# XMICRO-VDP_V1_1.net
KiCad netlist of a schematic drawn in EAGLE
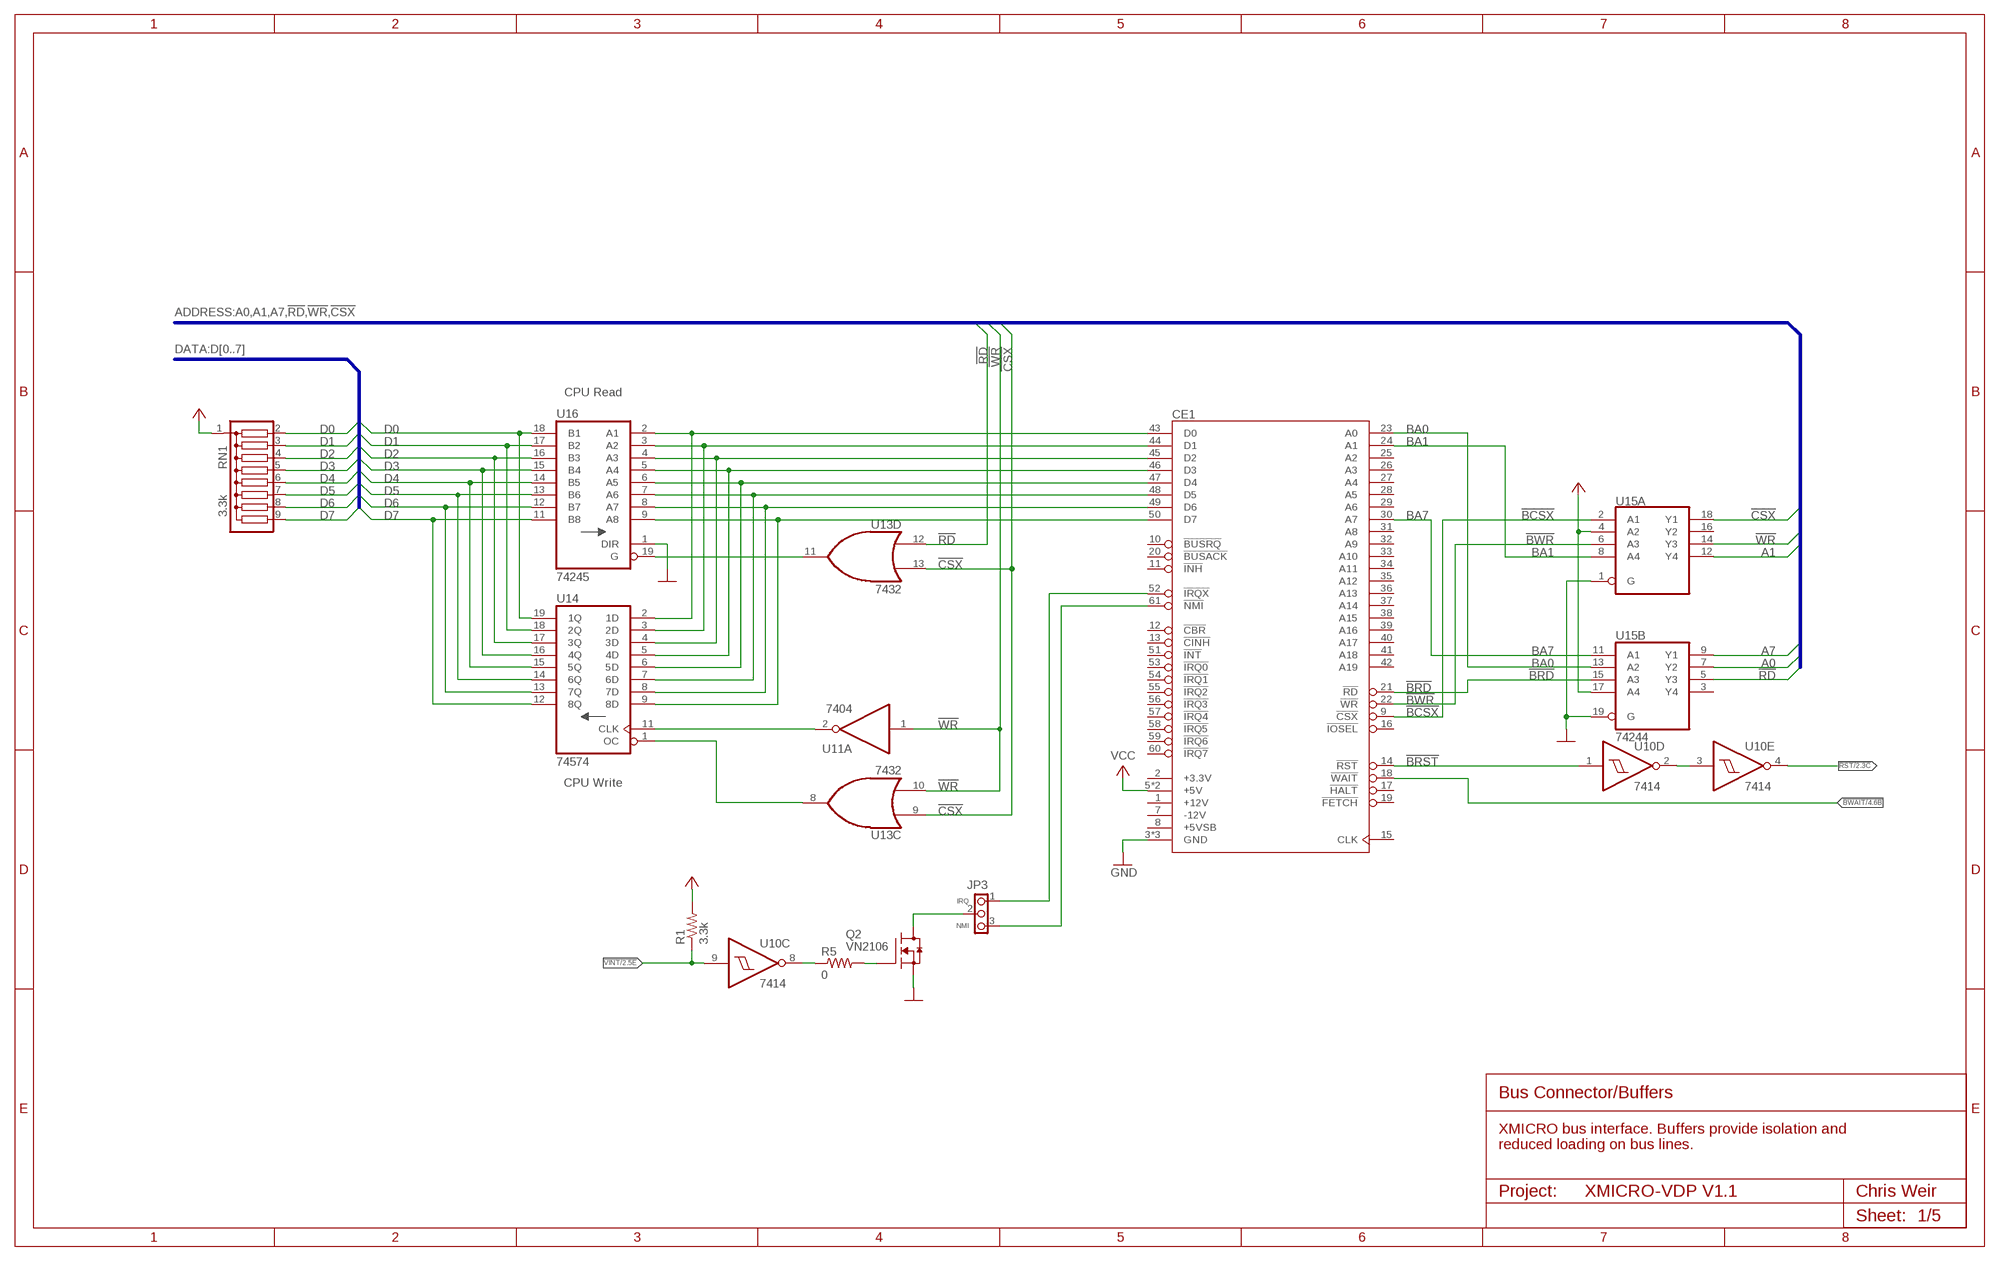
[diagram p0: schematic, sheet 1]
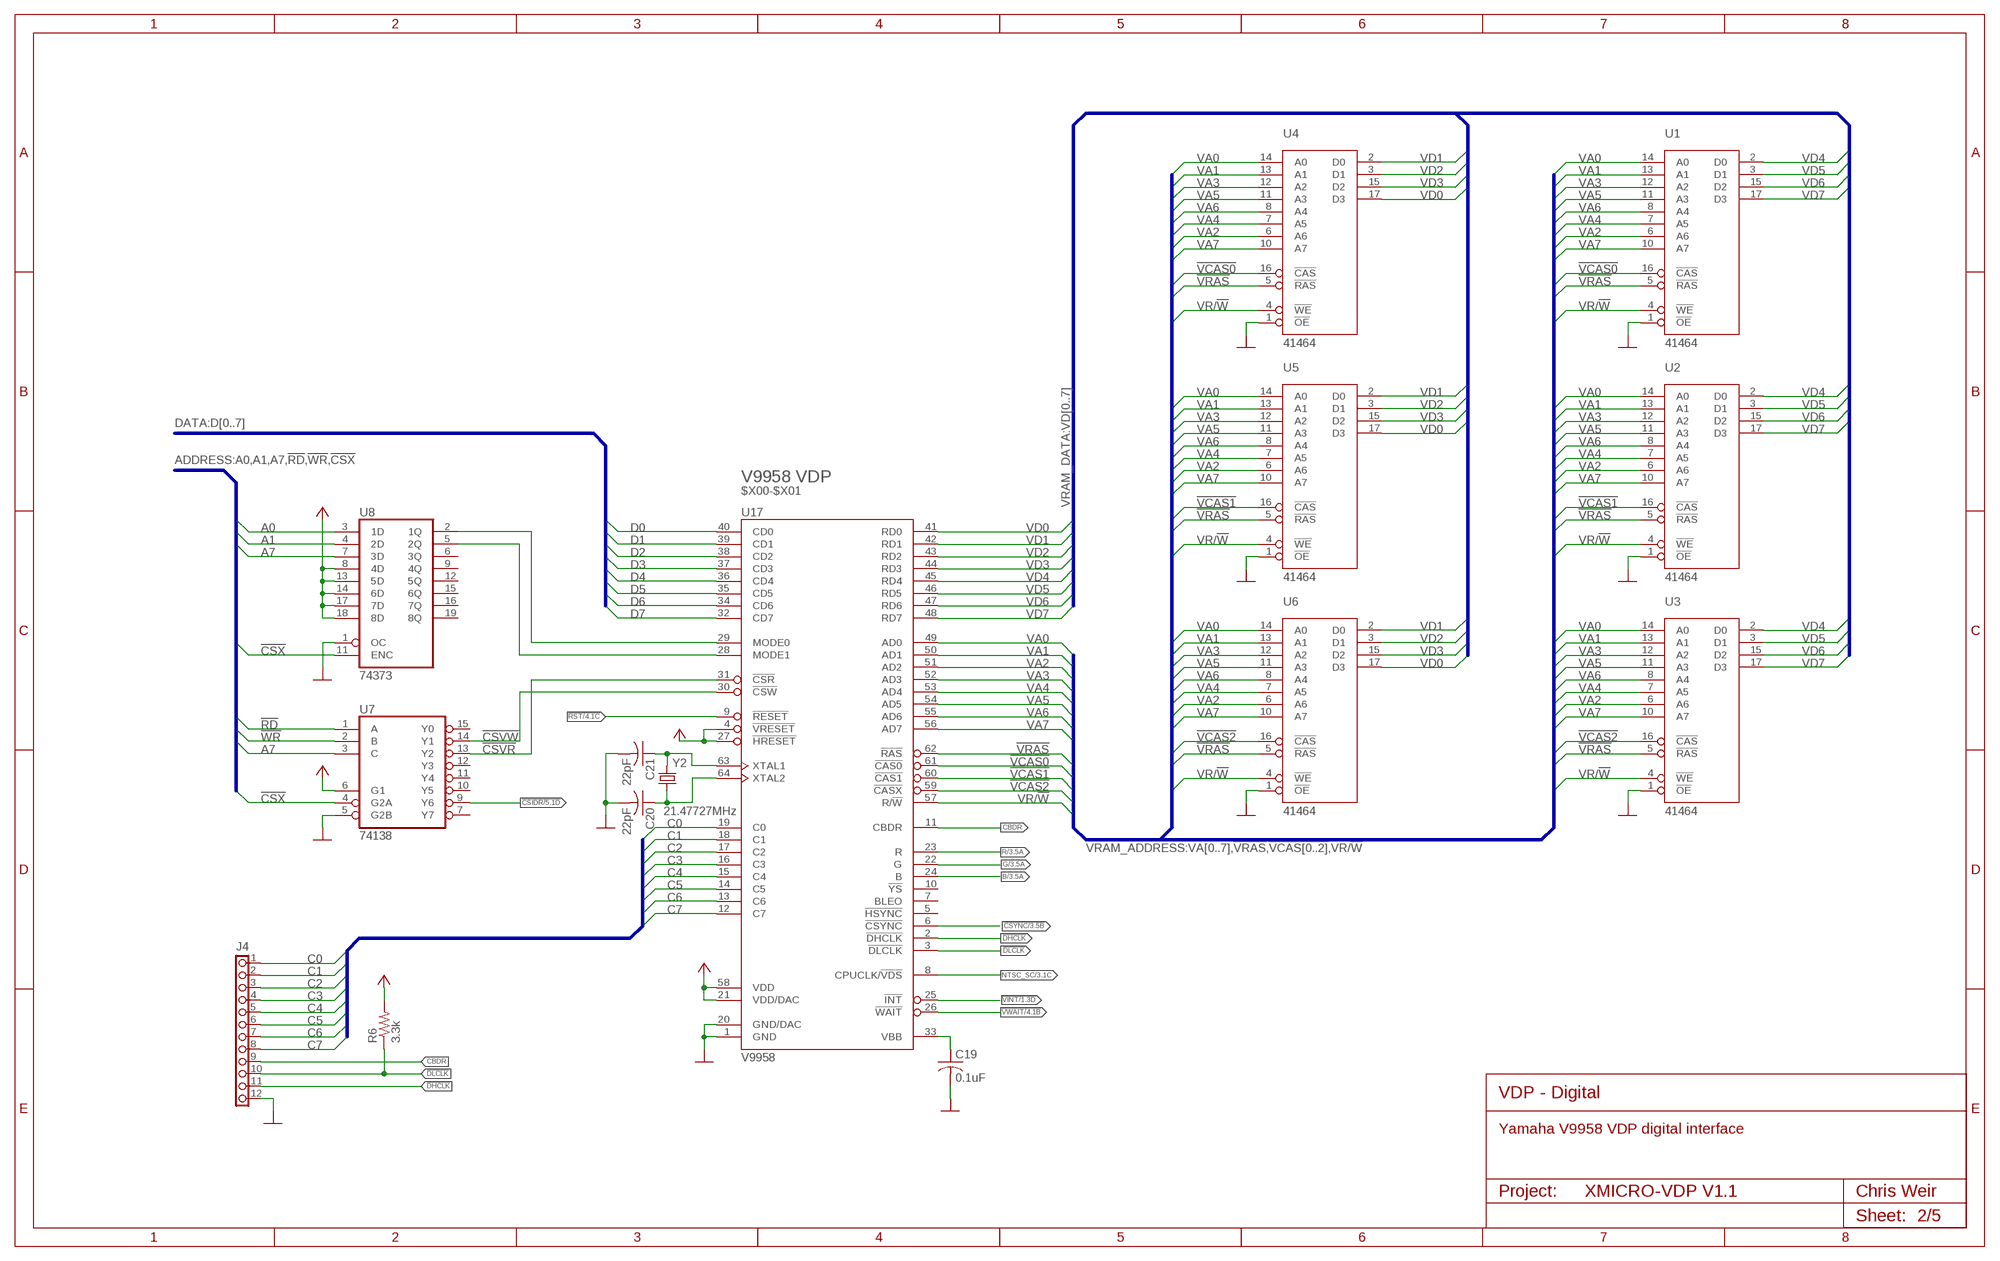
[diagram p1: schematic, sheet 2]
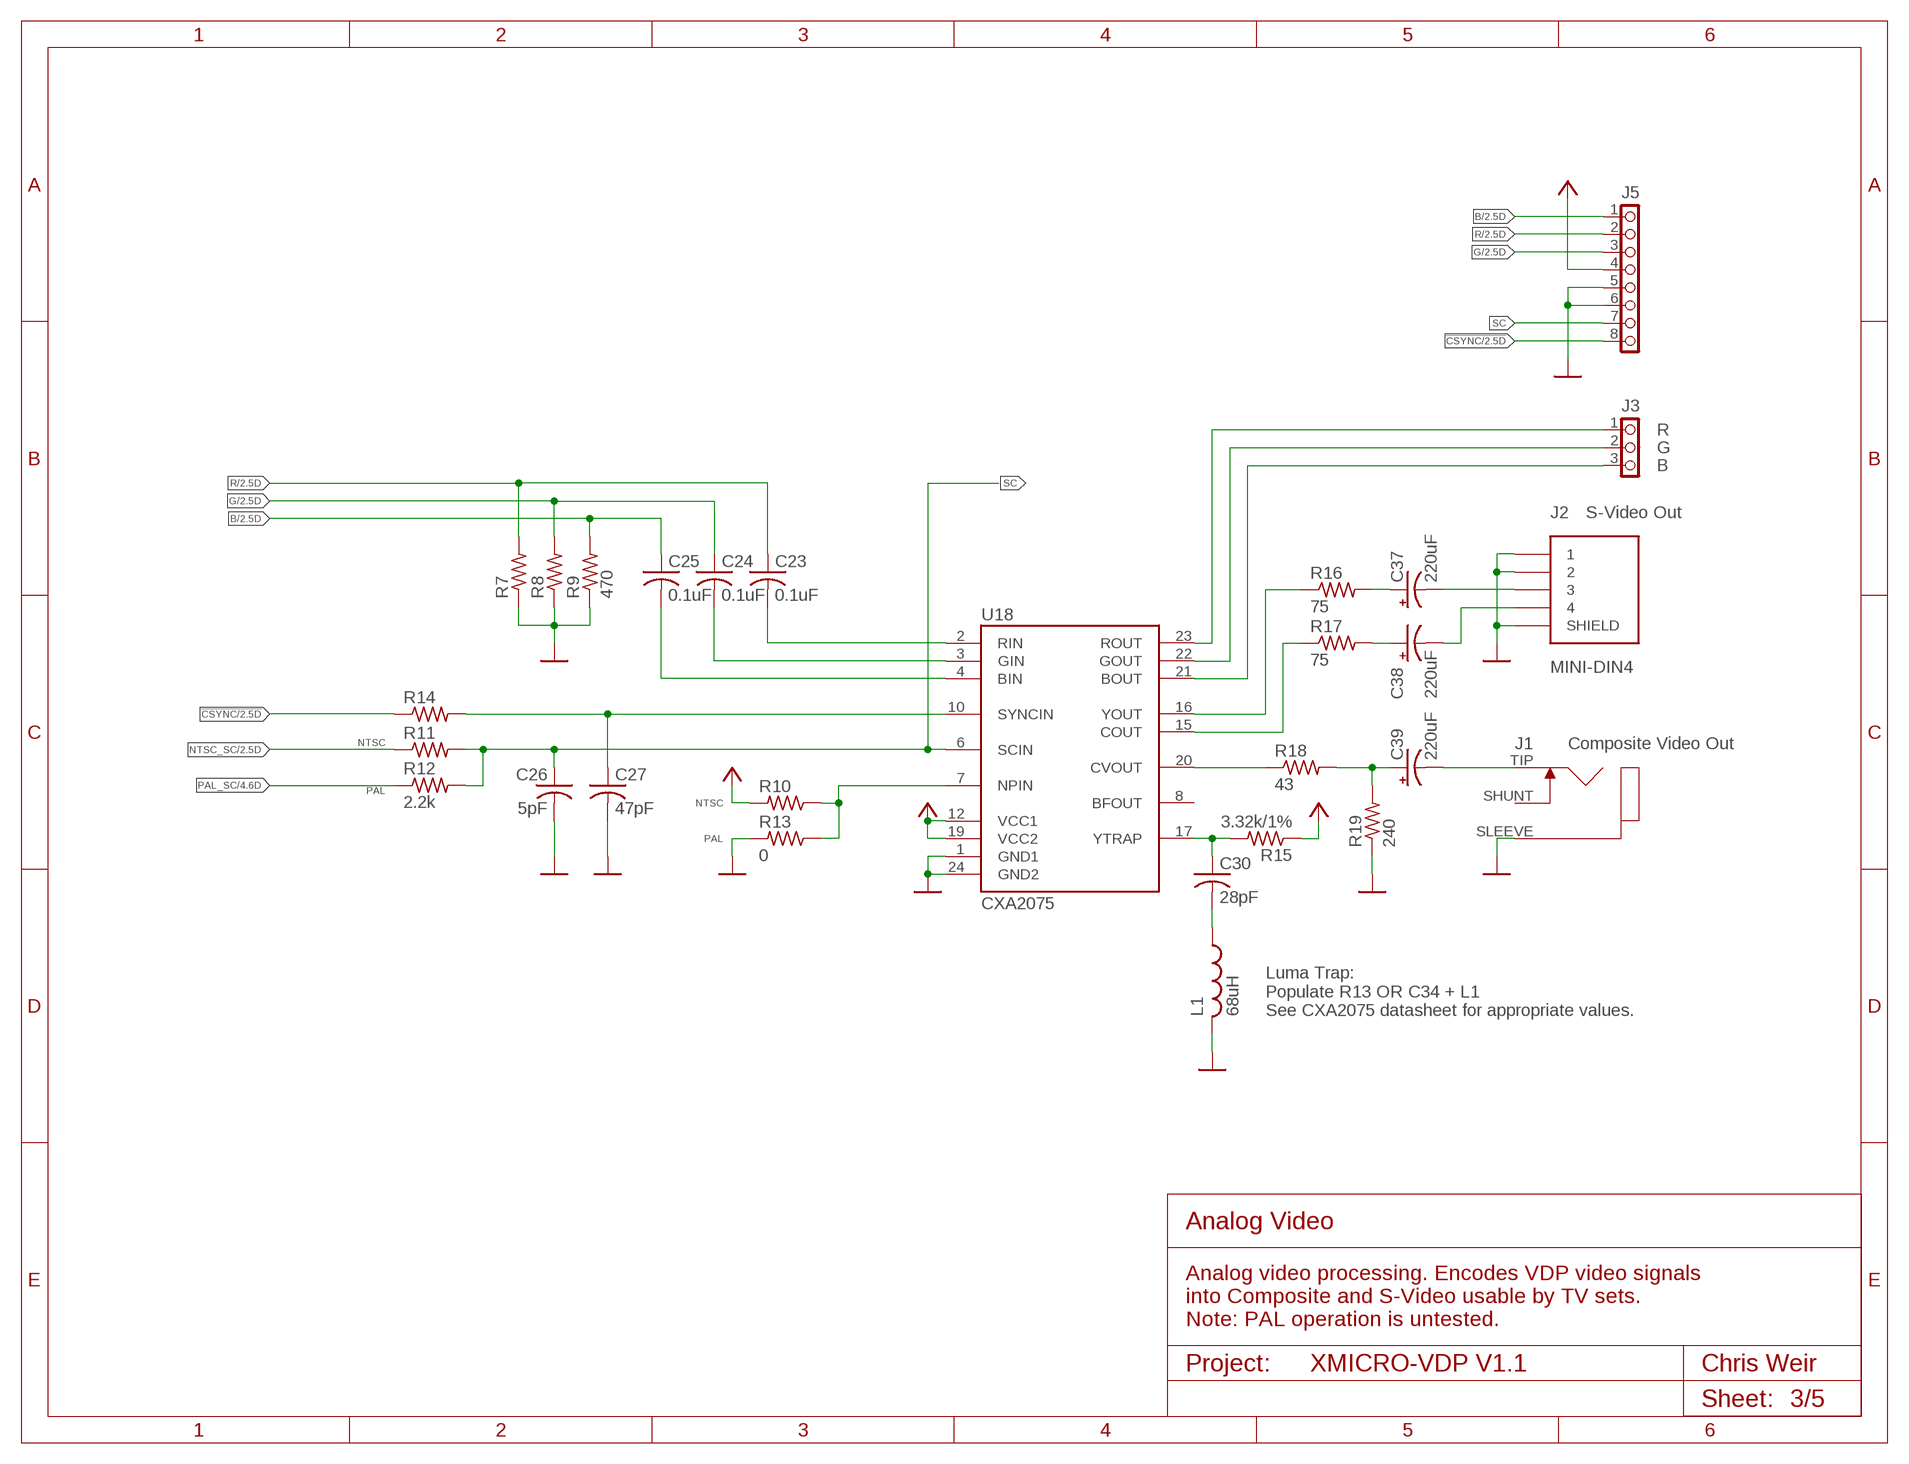
[diagram p2: schematic, sheet 3]
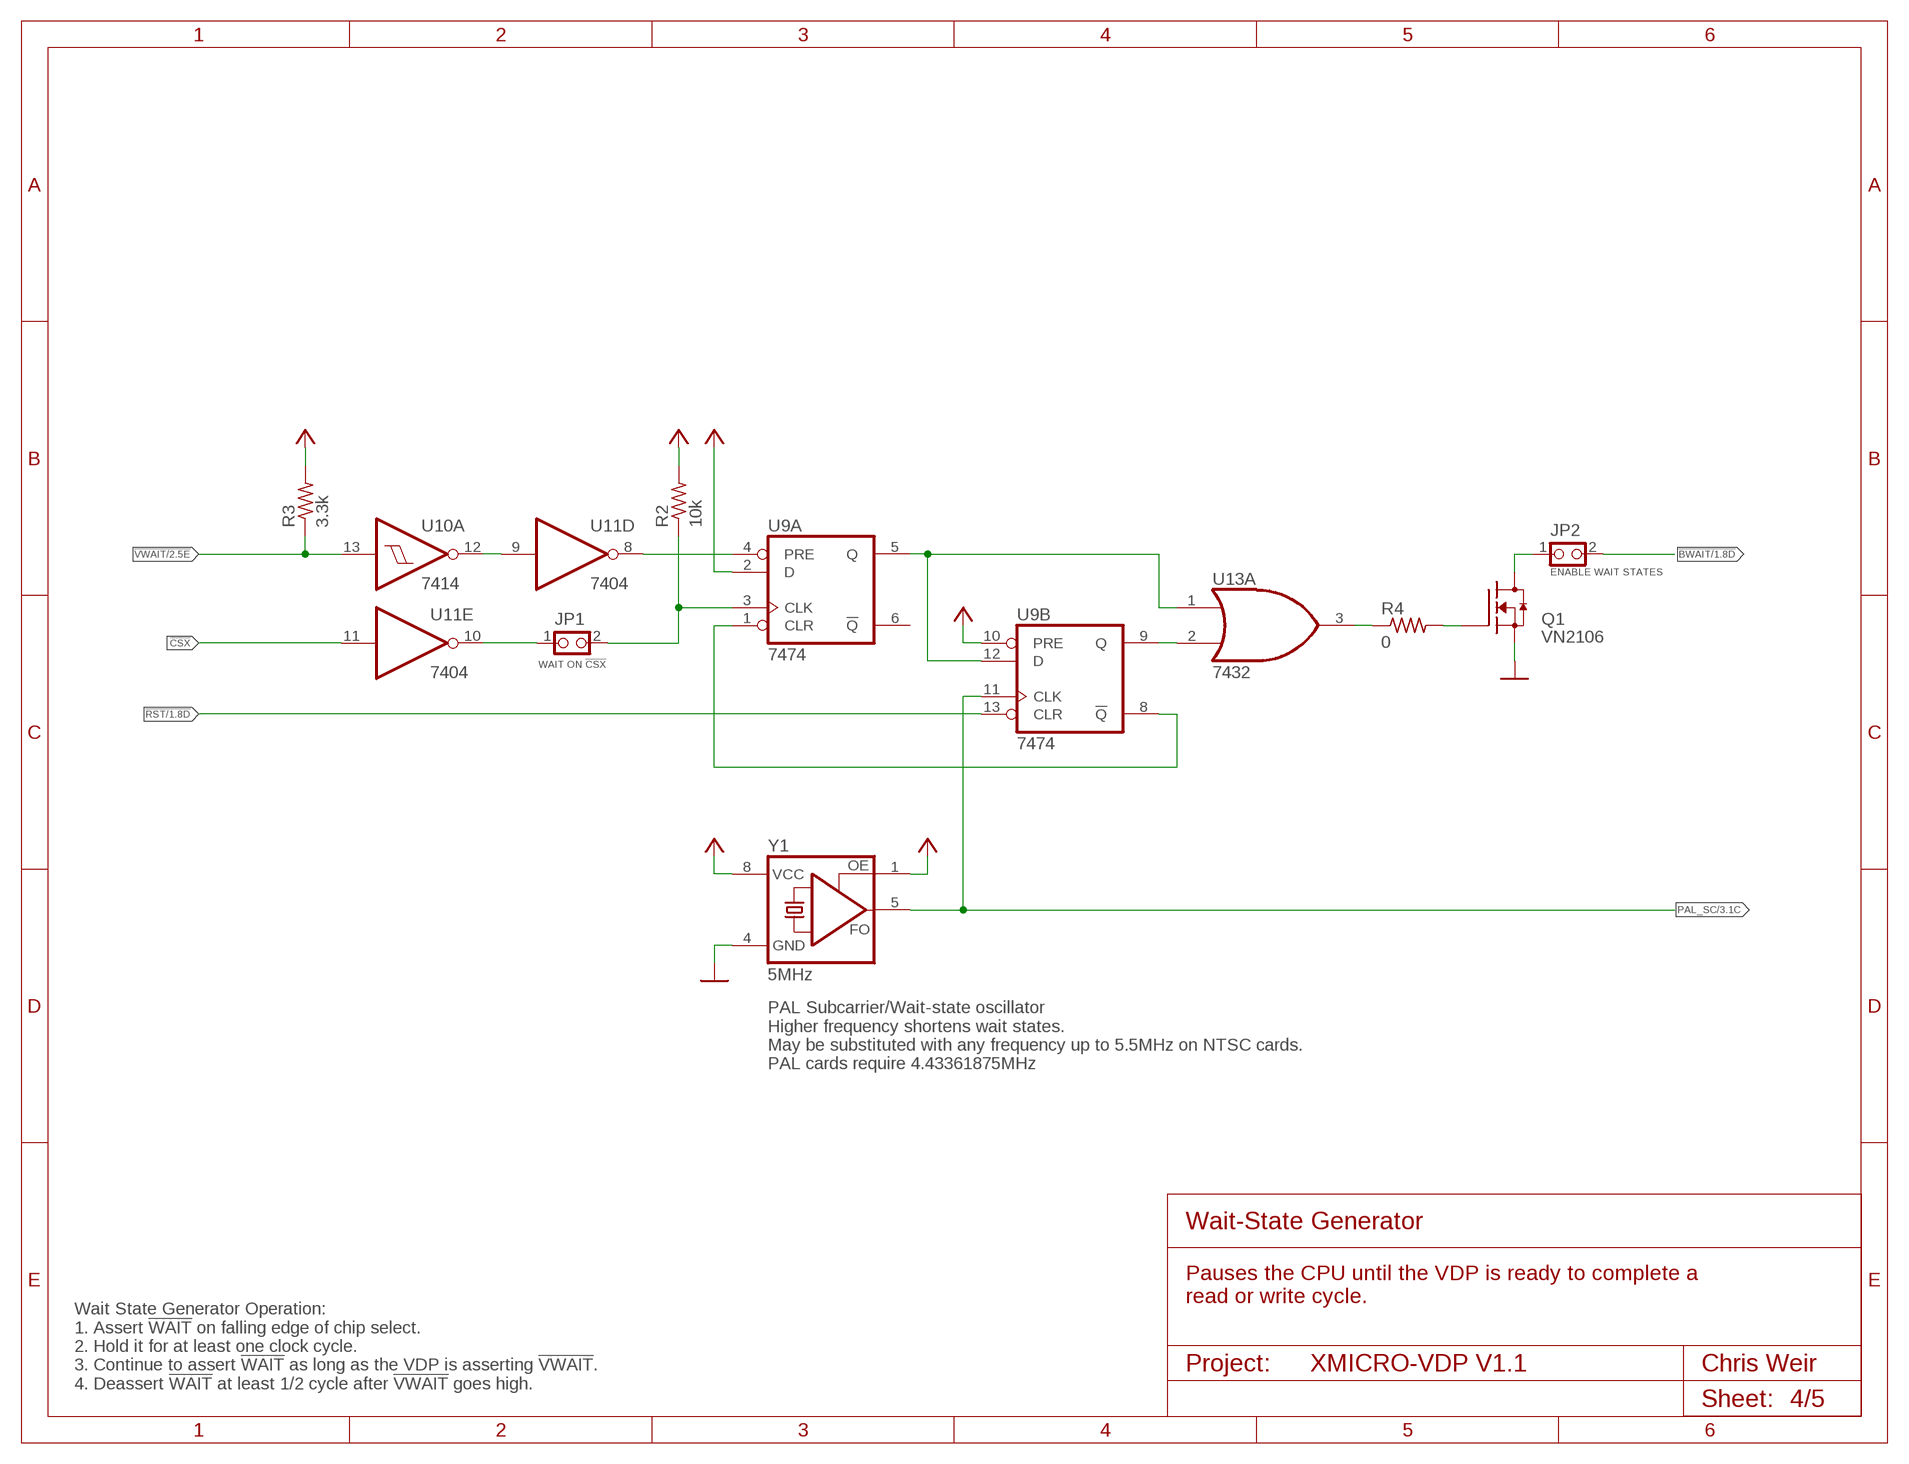
[diagram p3: schematic, sheet 4]
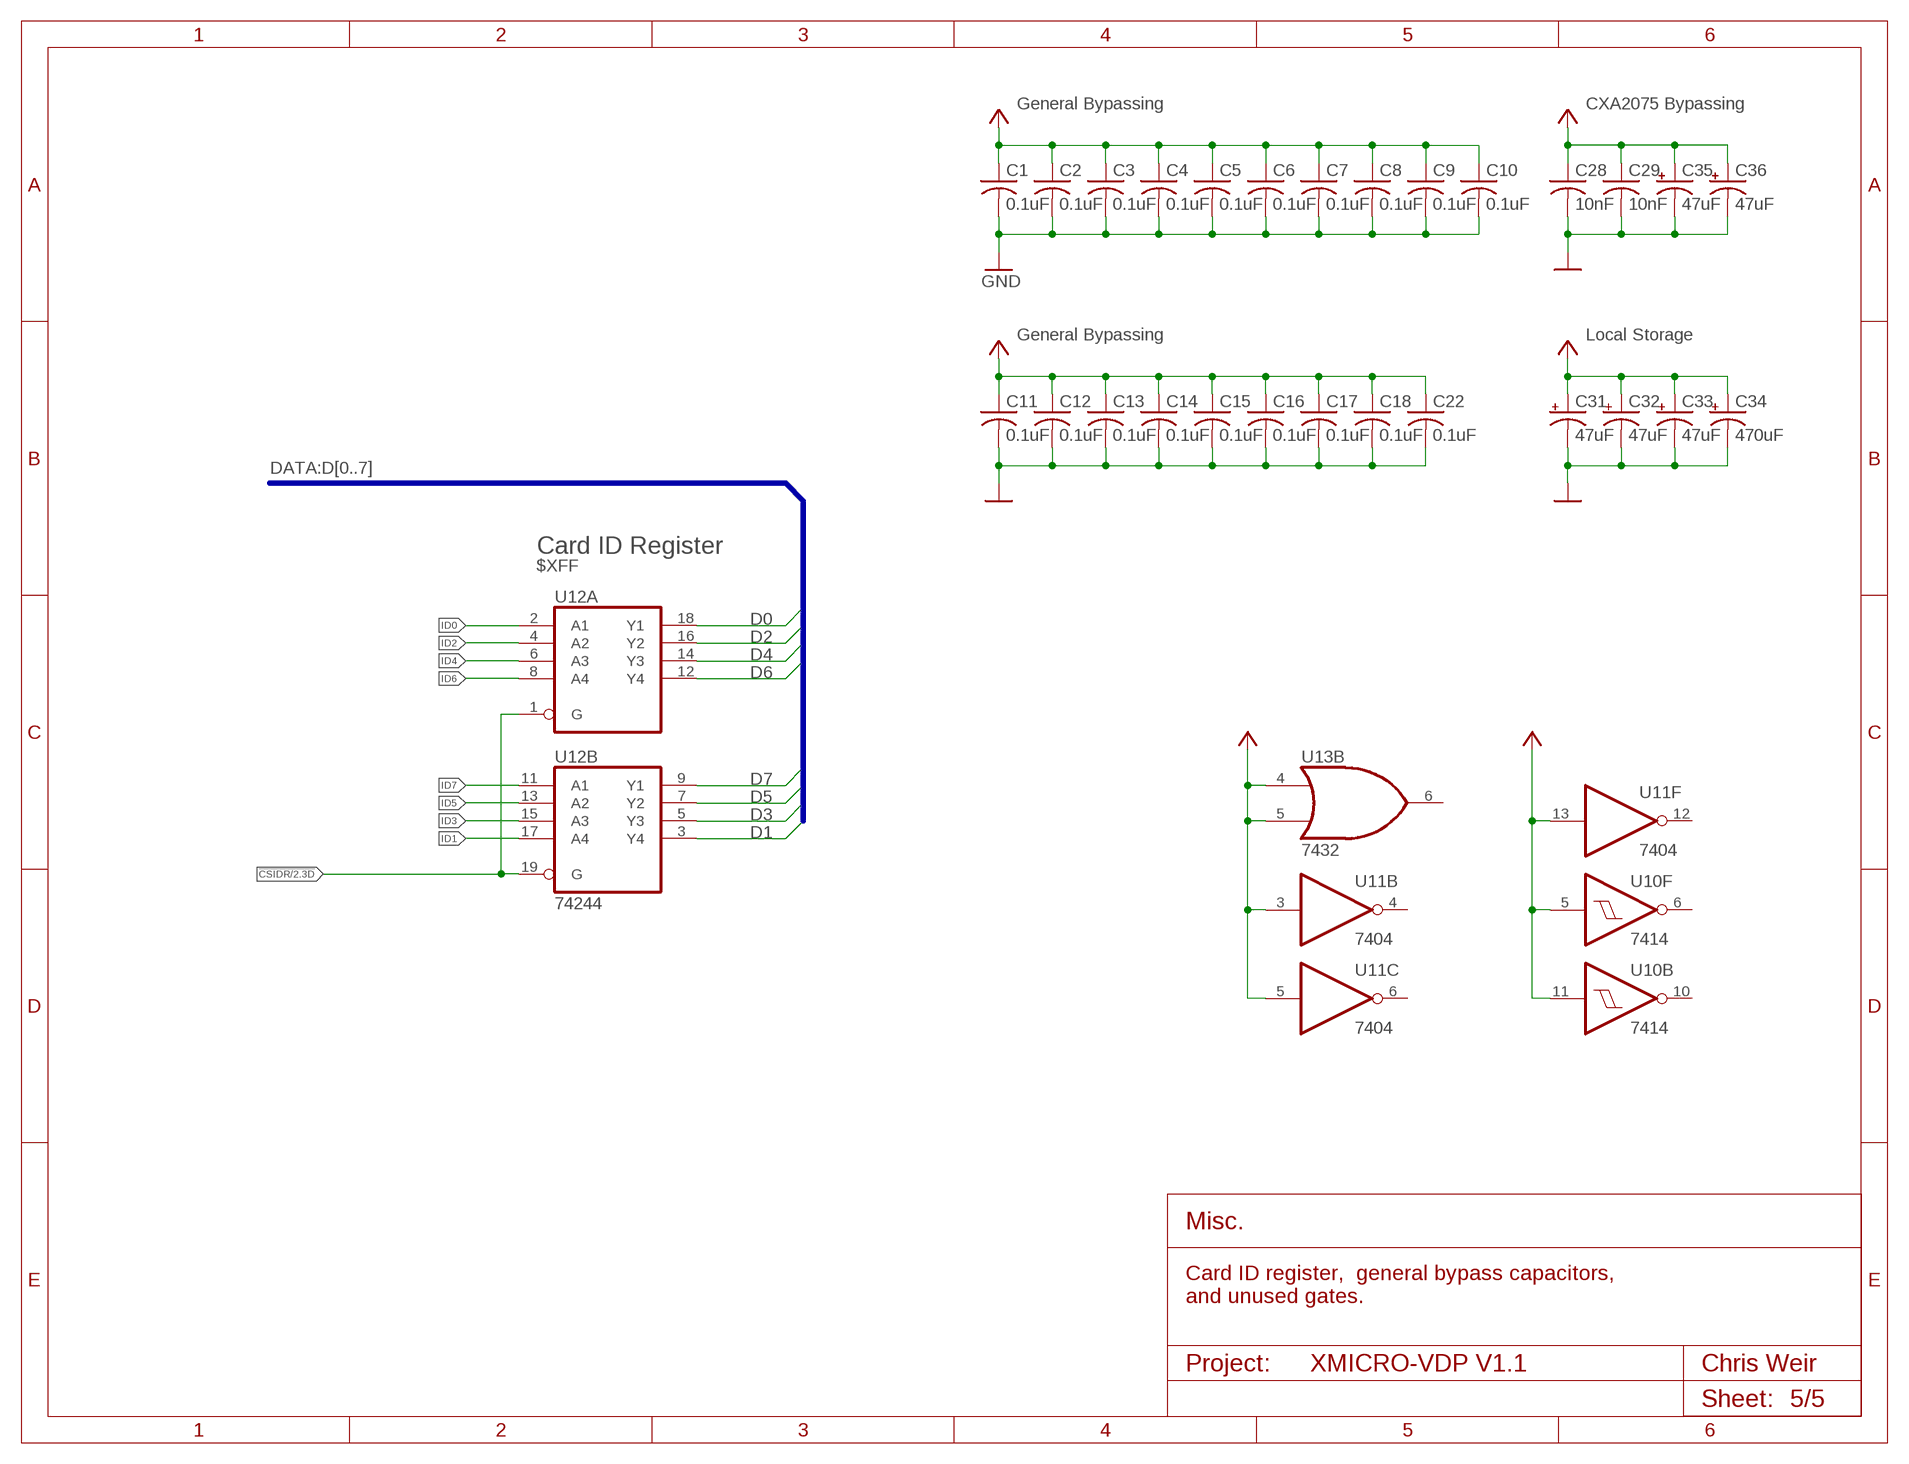
[diagram p4: schematic, sheet 5]

(export (version "E")
  (design (tool "Eeschema 10.0.6"))
  (components
    (comp (ref "C23")
      (value "0.1uF")
      (footprint "eagle-import:C100")
      (libsource (lib "eagle-import") (part "C-US100"))
    )
    (comp (ref "C24")
      (value "0.1uF")
      (footprint "eagle-import:C100")
      (libsource (lib "eagle-import") (part "C-US100"))
    )
    (comp (ref "C25")
      (value "0.1uF")
      (footprint "eagle-import:C100")
      (libsource (lib "eagle-import") (part "C-US100"))
    )
    (comp (ref "C26")
      (value "5pF")
      (footprint "eagle-import:C100")
      (libsource (lib "eagle-import") (part "C-US100"))
    )
    (comp (ref "C27")
      (value "47pF")
      (footprint "eagle-import:C100")
      (libsource (lib "eagle-import") (part "C-US100"))
    )
    (comp (ref "C30")
      (value "28pF")
      (footprint "eagle-import:C100")
      (libsource (lib "eagle-import") (part "C-US100"))
    )
    (comp (ref "C37")
      (value "220uF")
      (footprint "eagle-import:E2,5-7")
      (libsource (lib "eagle-import") (part "CPOL-USE2.5-7"))
    )
    (comp (ref "C38")
      (value "220uF")
      (footprint "eagle-import:E2,5-7")
      (libsource (lib "eagle-import") (part "CPOL-USE2.5-7"))
    )
    (comp (ref "C39")
      (value "220uF")
      (footprint "eagle-import:E2,5-7")
      (libsource (lib "eagle-import") (part "CPOL-USE2.5-7"))
    )
    (comp (ref "J1")
      (value "PJRAN1XU04AUX")
      (footprint "eagle-import:PJRAN1")
      (libsource (lib "eagle-import") (part "PJRAN1"))
    )
    (comp (ref "J2")
      (value "MINI-DIN4")
      (footprint "eagle-import:MINI-DIN4")
      (libsource (lib "eagle-import") (part "MINI-DIN4"))
    )
    (comp (ref "J3")
      (value "PINHD1X3")
      (footprint "eagle-import:1X03")
      (libsource (lib "eagle-import") (part "PINHD1X3"))
    )
    (comp (ref "J5")
      (value "PINHD-1X8")
      (footprint "eagle-import:1X08")
      (libsource (lib "eagle-import") (part "PINHD-1X8"))
    )
    (comp (ref "L1")
      (value "68uH")
      (footprint "eagle-import:0207_10")
      (libsource (lib "eagle-import") (part "L-US0207/10"))
    )
    (comp (ref "R7")
      (value "470")
      (footprint "eagle-import:0207_10")
      (libsource (lib "eagle-import") (part "R-US_0207/10"))
    )
    (comp (ref "R8")
      (value "470")
      (footprint "eagle-import:0207_10")
      (libsource (lib "eagle-import") (part "R-US_0207/10"))
    )
    (comp (ref "R9")
      (value "470")
      (footprint "eagle-import:0207_10")
      (libsource (lib "eagle-import") (part "R-US_0207/10"))
    )
    (comp (ref "R10")
      (value "0")
      (footprint "eagle-import:0207_10")
      (libsource (lib "eagle-import") (part "R-US_0207/10"))
    )
    (comp (ref "R11")
      (value "2.2k")
      (footprint "eagle-import:0207_10")
      (libsource (lib "eagle-import") (part "R-US_0207/10"))
    )
    (comp (ref "R12")
      (value "2.2k")
      (footprint "eagle-import:0207_10")
      (libsource (lib "eagle-import") (part "R-US_0207/10"))
    )
    (comp (ref "R13")
      (value "0")
      (footprint "eagle-import:0207_10")
      (libsource (lib "eagle-import") (part "R-US_0207/10"))
    )
    (comp (ref "R14")
      (value "2.2k")
      (footprint "eagle-import:0207_10")
      (libsource (lib "eagle-import") (part "R-US_0207/10"))
    )
    (comp (ref "R15")
      (value "3.32k/1%")
      (footprint "eagle-import:0207_10")
      (libsource (lib "eagle-import") (part "R-US_0207/10"))
    )
    (comp (ref "R16")
      (value "75")
      (footprint "eagle-import:0207_10")
      (libsource (lib "eagle-import") (part "R-US_0207/10"))
    )
    (comp (ref "R17")
      (value "75")
      (footprint "eagle-import:0207_10")
      (libsource (lib "eagle-import") (part "R-US_0207/10"))
    )
    (comp (ref "R18")
      (value "43")
      (footprint "eagle-import:0207_10")
      (libsource (lib "eagle-import") (part "R-US_0207/10"))
    )
    (comp (ref "R19")
      (value "240")
      (footprint "eagle-import:0207_10")
      (libsource (lib "eagle-import") (part "R-US_0207/10"))
    )
    (comp (ref "U18")
      (value "CXA2075")
      (footprint "eagle-import:SOP-24")
      (libsource (lib "eagle-import") (part "CXA2075"))
    )
    (comp (ref "JP1")
      (value "PINHD-1X2THRU")
      (footprint "eagle-import:1X02")
      (libsource (lib "eagle-import") (part "PINHD-1X2THRU"))
    )
    (comp (ref "JP2")
      (value "PINHD-1X2THRU")
      (footprint "eagle-import:1X02")
      (libsource (lib "eagle-import") (part "PINHD-1X2THRU"))
    )
    (comp (ref "Q1")
      (value "VN2106")
      (footprint "eagle-import:TO92")
      (libsource (lib "eagle-import") (part "VN2106"))
    )
    (comp (ref "R2")
      (value "10k")
      (footprint "eagle-import:0207_10")
      (libsource (lib "eagle-import") (part "R-US_0207/10"))
    )
    (comp (ref "R3")
      (value "3.3k")
      (footprint "eagle-import:0207_10")
      (libsource (lib "eagle-import") (part "R-US_0207/10"))
    )
    (comp (ref "R4")
      (value "0")
      (footprint "eagle-import:0207_10")
      (libsource (lib "eagle-import") (part "R-US_0207/10"))
    )
    (comp (ref "U9")
      (value "7474")
      (footprint "eagle-import:DIL14")
      (libsource (lib "eagle-import") (part "7474NLS"))
    )
    (comp (ref "U10")
      (value "7414")
      (footprint "eagle-import:DIL14")
      (libsource (lib "eagle-import") (part "7414NLS"))
    )
    (comp (ref "U11")
      (value "7404")
      (footprint "eagle-import:DIL14")
      (libsource (lib "eagle-import") (part "7404NLS"))
    )
    (comp (ref "U13")
      (value "7432")
      (footprint "eagle-import:DIL14")
      (libsource (lib "eagle-import") (part "7432NLS"))
    )
    (comp (ref "Y1")
      (value "5MHz")
      (footprint "eagle-import:DIL08S")
      (libsource (lib "eagle-import") (part "OSC-OE"))
    )
    (comp (ref "CE1")
      (value "XMICRO-BUS-EDGE62M")
      (footprint "eagle-import:EDGE62M")
      (libsource (lib "eagle-import") (part "XMICRO-BUS-EDGE62M"))
    )
    (comp (ref "JP3")
      (value "PINHD1X3THRU")
      (footprint "eagle-import:1X03")
      (libsource (lib "eagle-import") (part "PINHD1X3THRU"))
    )
    (comp (ref "Q2")
      (value "VN2106")
      (footprint "eagle-import:TO92")
      (libsource (lib "eagle-import") (part "VN2106"))
    )
    (comp (ref "R1")
      (value "3.3k")
      (footprint "eagle-import:0207_10")
      (libsource (lib "eagle-import") (part "R-US_0207/10"))
    )
    (comp (ref "R5")
      (value "0")
      (footprint "eagle-import:0207_10")
      (libsource (lib "eagle-import") (part "R-US_0207/10"))
    )
    (comp (ref "RN1")
      (value "3.3k")
      (footprint "eagle-import:SIL9")
      (libsource (lib "eagle-import") (part "RN8"))
    )
    (comp (ref "U14")
      (value "74574")
      (footprint "eagle-import:DIL20")
      (libsource (lib "eagle-import") (part "74574NHC"))
    )
    (comp (ref "U15")
      (value "74244")
      (footprint "eagle-import:DIL20")
      (libsource (lib "eagle-import") (part "74244NLS"))
    )
    (comp (ref "U16")
      (value "74245")
      (footprint "eagle-import:DIL20")
      (libsource (lib "eagle-import") (part "74245NLS"))
    )
    (comp (ref "C19")
      (value "0.1uF")
      (footprint "eagle-import:C100")
      (libsource (lib "eagle-import") (part "C-US100"))
    )
    (comp (ref "C20")
      (value "22pF")
      (footprint "eagle-import:C100")
      (libsource (lib "eagle-import") (part "C-US100"))
    )
    (comp (ref "C21")
      (value "22pF")
      (footprint "eagle-import:C100")
      (libsource (lib "eagle-import") (part "C-US100"))
    )
    (comp (ref "J4")
      (value "PINHD-2X6")
      (footprint "eagle-import:2X06")
      (libsource (lib "eagle-import") (part "PINHD-2X6"))
    )
    (comp (ref "R6")
      (value "3.3k")
      (footprint "eagle-import:0207_10")
      (libsource (lib "eagle-import") (part "R-US_0207/10"))
    )
    (comp (ref "U1")
      (value "41464")
      (footprint "eagle-import:DIL18")
      (libsource (lib "eagle-import") (part "41464"))
    )
    (comp (ref "U2")
      (value "41464")
      (footprint "eagle-import:DIL18")
      (libsource (lib "eagle-import") (part "41464"))
    )
    (comp (ref "U3")
      (value "41464")
      (footprint "eagle-import:DIL18")
      (libsource (lib "eagle-import") (part "41464"))
    )
    (comp (ref "U4")
      (value "41464")
      (footprint "eagle-import:DIL18")
      (libsource (lib "eagle-import") (part "41464"))
    )
    (comp (ref "U5")
      (value "41464")
      (footprint "eagle-import:DIL18")
      (libsource (lib "eagle-import") (part "41464"))
    )
    (comp (ref "U6")
      (value "41464")
      (footprint "eagle-import:DIL18")
      (libsource (lib "eagle-import") (part "41464"))
    )
    (comp (ref "U7")
      (value "74138")
      (footprint "eagle-import:DIL16")
      (libsource (lib "eagle-import") (part "74138NS"))
    )
    (comp (ref "U8")
      (value "74373")
      (footprint "eagle-import:DIL20")
      (libsource (lib "eagle-import") (part "74373NLS"))
    )
    (comp (ref "U17")
      (value "V9958")
      (footprint "eagle-import:SDIP64")
      (libsource (lib "eagle-import") (part "V9958"))
    )
    (comp (ref "Y2")
      (value "21.47727MHz")
      (footprint "eagle-import:HC-49US")
      (libsource (lib "eagle-import") (part "CRYSTAL"))
    )
    (comp (ref "C1")
      (value "0.1uF")
      (footprint "eagle-import:C100")
      (libsource (lib "eagle-import") (part "C-US100"))
    )
    (comp (ref "C2")
      (value "0.1uF")
      (footprint "eagle-import:C100")
      (libsource (lib "eagle-import") (part "C-US100"))
    )
    (comp (ref "C3")
      (value "0.1uF")
      (footprint "eagle-import:C100")
      (libsource (lib "eagle-import") (part "C-US100"))
    )
    (comp (ref "C4")
      (value "0.1uF")
      (footprint "eagle-import:C100")
      (libsource (lib "eagle-import") (part "C-US100"))
    )
    (comp (ref "C5")
      (value "0.1uF")
      (footprint "eagle-import:C100")
      (libsource (lib "eagle-import") (part "C-US100"))
    )
    (comp (ref "C6")
      (value "0.1uF")
      (footprint "eagle-import:C100")
      (libsource (lib "eagle-import") (part "C-US100"))
    )
    (comp (ref "C7")
      (value "0.1uF")
      (footprint "eagle-import:C100")
      (libsource (lib "eagle-import") (part "C-US100"))
    )
    (comp (ref "C8")
      (value "0.1uF")
      (footprint "eagle-import:C100")
      (libsource (lib "eagle-import") (part "C-US100"))
    )
    (comp (ref "C9")
      (value "0.1uF")
      (footprint "eagle-import:C100")
      (libsource (lib "eagle-import") (part "C-US100"))
    )
    (comp (ref "C10")
      (value "0.1uF")
      (footprint "eagle-import:C100")
      (libsource (lib "eagle-import") (part "C-US100"))
    )
    (comp (ref "C11")
      (value "0.1uF")
      (footprint "eagle-import:C100")
      (libsource (lib "eagle-import") (part "C-US100"))
    )
    (comp (ref "C12")
      (value "0.1uF")
      (footprint "eagle-import:C100")
      (libsource (lib "eagle-import") (part "C-US100"))
    )
    (comp (ref "C13")
      (value "0.1uF")
      (footprint "eagle-import:C100")
      (libsource (lib "eagle-import") (part "C-US100"))
    )
    (comp (ref "C14")
      (value "0.1uF")
      (footprint "eagle-import:C100")
      (libsource (lib "eagle-import") (part "C-US100"))
    )
    (comp (ref "C15")
      (value "0.1uF")
      (footprint "eagle-import:C100")
      (libsource (lib "eagle-import") (part "C-US100"))
    )
    (comp (ref "C16")
      (value "0.1uF")
      (footprint "eagle-import:C100")
      (libsource (lib "eagle-import") (part "C-US100"))
    )
    (comp (ref "C17")
      (value "0.1uF")
      (footprint "eagle-import:C100")
      (libsource (lib "eagle-import") (part "C-US100"))
    )
    (comp (ref "C18")
      (value "0.1uF")
      (footprint "eagle-import:C100")
      (libsource (lib "eagle-import") (part "C-US100"))
    )
    (comp (ref "C22")
      (value "0.1uF")
      (footprint "eagle-import:C100")
      (libsource (lib "eagle-import") (part "C-US100"))
    )
    (comp (ref "C28")
      (value "10nF")
      (footprint "eagle-import:C100")
      (libsource (lib "eagle-import") (part "C-US100"))
    )
    (comp (ref "C29")
      (value "10nF")
      (footprint "eagle-import:C050-024X044")
      (libsource (lib "eagle-import") (part "C-US050-024X044"))
    )
    (comp (ref "C31")
      (value "47uF")
      (footprint "eagle-import:E2,5-6")
      (libsource (lib "eagle-import") (part "CPOL-USE2.5-6"))
    )
    (comp (ref "C32")
      (value "47uF")
      (footprint "eagle-import:E2,5-6")
      (libsource (lib "eagle-import") (part "CPOL-USE2.5-6"))
    )
    (comp (ref "C33")
      (value "47uF")
      (footprint "eagle-import:E2,5-6")
      (libsource (lib "eagle-import") (part "CPOL-USE2.5-6"))
    )
    (comp (ref "C34")
      (value "470uF")
      (footprint "eagle-import:C-10-5")
      (libsource (lib "eagle-import") (part "CPOL-US-10-5"))
    )
    (comp (ref "C35")
      (value "47uF")
      (footprint "eagle-import:E2,5-6")
      (libsource (lib "eagle-import") (part "CPOL-USE2.5-6"))
    )
    (comp (ref "C36")
      (value "47uF")
      (footprint "eagle-import:E2,5-6")
      (libsource (lib "eagle-import") (part "CPOL-USE2.5-6"))
    )
    (comp (ref "U12")
      (value "74244")
      (footprint "eagle-import:DIL20")
      (libsource (lib "eagle-import") (part "74244NLS"))
    )
  )
  (nets
    (net (code "42") (name "A0") (class "Default")
      (node (ref "U15") (pin "7") (pinfunction "Y2_7") (pintype "tri_state"))
      (node (ref "U8") (pin "3") (pinfunction "1D_3") (pintype "input"))
    )
    (net (code "43") (name "A1") (class "Default")
      (node (ref "U15") (pin "12") (pinfunction "Y4_12") (pintype "tri_state"))
      (node (ref "U8") (pin "4") (pinfunction "2D_4") (pintype "input"))
    )
    (net (code "44") (name "A7") (class "Default")
      (node (ref "U15") (pin "9") (pinfunction "Y1_9") (pintype "tri_state"))
      (node (ref "U7") (pin "3") (pinfunction "C_3") (pintype "input"))
      (node (ref "U8") (pin "7") (pinfunction "3D_7") (pintype "input"))
    )
    (net (code "45") (name "B") (class "Default")
      (node (ref "C25") (pin "P$1") (pinfunction "1_P$1") (pintype "passive"))
      (node (ref "J5") (pin "1") (pinfunction "1_1") (pintype "passive"))
      (node (ref "R9") (pin "2") (pinfunction "2_2") (pintype "passive"))
      (node (ref "U17") (pin "24") (pinfunction "B_24") (pintype "output"))
    )
    (net (code "46") (name "BA0") (class "Default")
      (node (ref "CE1") (pin "23") (pinfunction "A0_23") (pintype "bidirectional"))
      (node (ref "U15") (pin "13") (pinfunction "A2_13") (pintype "input"))
    )
    (net (code "47") (name "BA1") (class "Default")
      (node (ref "CE1") (pin "24") (pinfunction "A1_24") (pintype "bidirectional"))
      (node (ref "U15") (pin "8") (pinfunction "A4_8") (pintype "input"))
    )
    (net (code "48") (name "BA7") (class "Default")
      (node (ref "CE1") (pin "30") (pinfunction "A7_30") (pintype "bidirectional"))
      (node (ref "U15") (pin "11") (pinfunction "A1_11") (pintype "input"))
    )
    (net (code "49") (name "C0") (class "Default")
      (node (ref "J4") (pin "1") (pinfunction "1_1") (pintype "passive"))
      (node (ref "U17") (pin "19") (pinfunction "C0_19") (pintype "bidirectional"))
    )
    (net (code "50") (name "C1") (class "Default")
      (node (ref "J4") (pin "2") (pinfunction "2_2") (pintype "passive"))
      (node (ref "U17") (pin "18") (pinfunction "C1_18") (pintype "bidirectional"))
    )
    (net (code "51") (name "C2") (class "Default")
      (node (ref "J4") (pin "3") (pinfunction "3_3") (pintype "passive"))
      (node (ref "U17") (pin "17") (pinfunction "C2_17") (pintype "bidirectional"))
    )
    (net (code "52") (name "C3") (class "Default")
      (node (ref "J4") (pin "4") (pinfunction "4_4") (pintype "passive"))
      (node (ref "U17") (pin "16") (pinfunction "C3_16") (pintype "bidirectional"))
    )
    (net (code "53") (name "C4") (class "Default")
      (node (ref "J4") (pin "5") (pinfunction "5_5") (pintype "passive"))
      (node (ref "U17") (pin "15") (pinfunction "C4_15") (pintype "bidirectional"))
    )
    (net (code "54") (name "C5") (class "Default")
      (node (ref "J4") (pin "6") (pinfunction "6_6") (pintype "passive"))
      (node (ref "U17") (pin "14") (pinfunction "C5_14") (pintype "bidirectional"))
    )
    (net (code "55") (name "C6") (class "Default")
      (node (ref "J4") (pin "7") (pinfunction "7_7") (pintype "passive"))
      (node (ref "U17") (pin "13") (pinfunction "C6_13") (pintype "bidirectional"))
    )
    (net (code "56") (name "C7") (class "Default")
      (node (ref "J4") (pin "8") (pinfunction "8_8") (pintype "passive"))
      (node (ref "U17") (pin "12") (pinfunction "C7_12") (pintype "bidirectional"))
    )
    (net (code "57") (name "CBDR") (class "Default")
      (node (ref "J4") (pin "9") (pinfunction "9_9") (pintype "passive"))
      (node (ref "U17") (pin "11") (pinfunction "CBDR_11") (pintype "output"))
    )
    (net (code "58") (name "D0") (class "Default")
      (node (ref "RN1") (pin "2") (pinfunction "2_2") (pintype "passive"))
      (node (ref "U12") (pin "18") (pinfunction "Y1_18") (pintype "tri_state"))
      (node (ref "U14") (pin "19") (pinfunction "1Q_19") (pintype "tri_state"))
      (node (ref "U16") (pin "18") (pinfunction "B1_18") (pintype "bidirectional"))
      (node (ref "U17") (pin "40") (pinfunction "CD0_40") (pintype "bidirectional"))
    )
    (net (code "59") (name "D1") (class "Default")
      (node (ref "RN1") (pin "3") (pinfunction "3_3") (pintype "passive"))
      (node (ref "U12") (pin "3") (pinfunction "Y4_3") (pintype "tri_state"))
      (node (ref "U14") (pin "18") (pinfunction "2Q_18") (pintype "tri_state"))
      (node (ref "U16") (pin "17") (pinfunction "B2_17") (pintype "bidirectional"))
      (node (ref "U17") (pin "39") (pinfunction "CD1_39") (pintype "bidirectional"))
    )
    (net (code "60") (name "D2") (class "Default")
      (node (ref "RN1") (pin "4") (pinfunction "4_4") (pintype "passive"))
      (node (ref "U12") (pin "16") (pinfunction "Y2_16") (pintype "tri_state"))
      (node (ref "U14") (pin "17") (pinfunction "3Q_17") (pintype "tri_state"))
      (node (ref "U16") (pin "16") (pinfunction "B3_16") (pintype "bidirectional"))
      (node (ref "U17") (pin "38") (pinfunction "CD2_38") (pintype "bidirectional"))
    )
    (net (code "61") (name "D3") (class "Default")
      (node (ref "RN1") (pin "5") (pinfunction "5_5") (pintype "passive"))
      (node (ref "U12") (pin "5") (pinfunction "Y3_5") (pintype "tri_state"))
      (node (ref "U14") (pin "16") (pinfunction "4Q_16") (pintype "tri_state"))
      (node (ref "U16") (pin "15") (pinfunction "B4_15") (pintype "bidirectional"))
      (node (ref "U17") (pin "37") (pinfunction "CD3_37") (pintype "bidirectional"))
    )
    (net (code "62") (name "D4") (class "Default")
      (node (ref "RN1") (pin "6") (pinfunction "6_6") (pintype "passive"))
      (node (ref "U12") (pin "14") (pinfunction "Y3_14") (pintype "tri_state"))
      (node (ref "U14") (pin "15") (pinfunction "5Q_15") (pintype "tri_state"))
      (node (ref "U16") (pin "14") (pinfunction "B5_14") (pintype "bidirectional"))
      (node (ref "U17") (pin "36") (pinfunction "CD4_36") (pintype "bidirectional"))
    )
    (net (code "63") (name "D5") (class "Default")
      (node (ref "RN1") (pin "7") (pinfunction "7_7") (pintype "passive"))
      (node (ref "U12") (pin "7") (pinfunction "Y2_7") (pintype "tri_state"))
      (node (ref "U14") (pin "14") (pinfunction "6Q_14") (pintype "tri_state"))
      (node (ref "U16") (pin "13") (pinfunction "B6_13") (pintype "bidirectional"))
      (node (ref "U17") (pin "35") (pinfunction "CD5_35") (pintype "bidirectional"))
    )
    (net (code "64") (name "D6") (class "Default")
      (node (ref "RN1") (pin "8") (pinfunction "8_8") (pintype "passive"))
      (node (ref "U12") (pin "12") (pinfunction "Y4_12") (pintype "tri_state"))
      (node (ref "U14") (pin "13") (pinfunction "7Q_13") (pintype "tri_state"))
      (node (ref "U16") (pin "12") (pinfunction "B7_12") (pintype "bidirectional"))
      (node (ref "U17") (pin "34") (pinfunction "CD6_34") (pintype "bidirectional"))
    )
    (net (code "65") (name "D7") (class "Default")
      (node (ref "RN1") (pin "9") (pinfunction "9_9") (pintype "passive"))
      (node (ref "U12") (pin "9") (pinfunction "Y1_9") (pintype "tri_state"))
      (node (ref "U14") (pin "12") (pinfunction "8Q_12") (pintype "tri_state"))
      (node (ref "U16") (pin "11") (pinfunction "B8_11") (pintype "bidirectional"))
      (node (ref "U17") (pin "32") (pinfunction "CD7_32") (pintype "bidirectional"))
    )
    (net (code "66") (name "G") (class "Default")
      (node (ref "C24") (pin "P$1") (pinfunction "1_P$1") (pintype "passive"))
      (node (ref "J5") (pin "3") (pinfunction "3_3") (pintype "passive"))
      (node (ref "R8") (pin "2") (pinfunction "2_2") (pintype "passive"))
      (node (ref "U17") (pin "22") (pinfunction "G_22") (pintype "output"))
    )
    (net (code "67") (name "GND") (class "Default")
      (node (ref "C1") (pin "P$2") (pinfunction "2_P$2") (pintype "passive"))
      (node (ref "C10") (pin "P$2") (pinfunction "2_P$2") (pintype "passive"))
      (node (ref "C11") (pin "P$2") (pinfunction "2_P$2") (pintype "passive"))
      (node (ref "C12") (pin "P$2") (pinfunction "2_P$2") (pintype "passive"))
      (node (ref "C13") (pin "P$2") (pinfunction "2_P$2") (pintype "passive"))
      (node (ref "C14") (pin "P$2") (pinfunction "2_P$2") (pintype "passive"))
      (node (ref "C15") (pin "P$2") (pinfunction "2_P$2") (pintype "passive"))
      (node (ref "C16") (pin "P$2") (pinfunction "2_P$2") (pintype "passive"))
      (node (ref "C17") (pin "P$2") (pinfunction "2_P$2") (pintype "passive"))
      (node (ref "C18") (pin "P$2") (pinfunction "2_P$2") (pintype "passive"))
      (node (ref "C19") (pin "P$2") (pinfunction "2_P$2") (pintype "passive"))
      (node (ref "C2") (pin "P$2") (pinfunction "2_P$2") (pintype "passive"))
      (node (ref "C20") (pin "P$2") (pinfunction "2_P$2") (pintype "passive"))
      (node (ref "C21") (pin "P$2") (pinfunction "2_P$2") (pintype "passive"))
      (node (ref "C22") (pin "P$2") (pinfunction "2_P$2") (pintype "passive"))
      (node (ref "C26") (pin "P$2") (pinfunction "2_P$2") (pintype "passive"))
      (node (ref "C27") (pin "P$2") (pinfunction "2_P$2") (pintype "passive"))
      (node (ref "C28") (pin "P$2") (pinfunction "2_P$2") (pintype "passive"))
      (node (ref "C29") (pin "2") (pinfunction "2_2") (pintype "passive"))
      (node (ref "C3") (pin "P$2") (pinfunction "2_P$2") (pintype "passive"))
      (node (ref "C31") (pin "-") (pinfunction "-_-") (pintype "passive"))
      (node (ref "C32") (pin "-") (pinfunction "-_-") (pintype "passive"))
      (node (ref "C33") (pin "-") (pinfunction "-_-") (pintype "passive"))
      (node (ref "C34") (pin "-") (pinfunction "-_-") (pintype "passive"))
      (node (ref "C35") (pin "-") (pinfunction "-_-") (pintype "passive"))
      (node (ref "C36") (pin "-") (pinfunction "-_-") (pintype "passive"))
      (node (ref "C4") (pin "P$2") (pinfunction "2_P$2") (pintype "passive"))
      (node (ref "C5") (pin "P$2") (pinfunction "2_P$2") (pintype "passive"))
      (node (ref "C6") (pin "P$2") (pinfunction "2_P$2") (pintype "passive"))
      (node (ref "C7") (pin "P$2") (pinfunction "2_P$2") (pintype "passive"))
      (node (ref "C8") (pin "P$2") (pinfunction "2_P$2") (pintype "passive"))
      (node (ref "C9") (pin "P$2") (pinfunction "2_P$2") (pintype "passive"))
      (node (ref "CE1") (pin "3") (pinfunction "GND_3") (pintype "bidirectional"))
      (node (ref "CE1") (pin "4") (pinfunction "GND_4") (pintype "bidirectional"))
      (node (ref "CE1") (pin "62") (pinfunction "GND_62") (pintype "bidirectional"))
      (node (ref "J1") (pin "SLEEVE") (pinfunction "SLEEVE_SLEEVE") (pintype "bidirectional"))
      (node (ref "J2") (pin "1") (pinfunction "1_1") (pintype "bidirectional"))
      (node (ref "J2") (pin "2") (pinfunction "2_2") (pintype "bidirectional"))
      (node (ref "J2") (pin "G$1") (pinfunction "SHIELD_G$1") (pintype "bidirectional"))
      (node (ref "J2") (pin "G$2") (pinfunction "SHIELD_G$2") (pintype "bidirectional"))
      (node (ref "J2") (pin "G$3") (pinfunction "SHIELD_G$3") (pintype "bidirectional"))
      (node (ref "J4") (pin "12") (pinfunction "12_12") (pintype "passive"))
      (node (ref "J5") (pin "5") (pinfunction "5_5") (pintype "passive"))
      (node (ref "J5") (pin "6") (pinfunction "6_6") (pintype "passive"))
      (node (ref "L1") (pin "2") (pinfunction "2_2") (pintype "passive"))
      (node (ref "Q1") (pin "1") (pinfunction "S_1") (pintype "passive"))
      (node (ref "Q2") (pin "1") (pinfunction "S_1") (pintype "passive"))
      (node (ref "R13") (pin "2") (pinfunction "2_2") (pintype "passive"))
      (node (ref "R19") (pin "1") (pinfunction "1_1") (pintype "passive"))
      (node (ref "R7") (pin "1") (pinfunction "1_1") (pintype "passive"))
      (node (ref "R8") (pin "1") (pinfunction "1_1") (pintype "passive"))
      (node (ref "R9") (pin "1") (pinfunction "1_1") (pintype "passive"))
      (node (ref "U1") (pin "1") (pinfunction "~{OE}_1") (pintype "input"))
      (node (ref "U15") (pin "1") (pinfunction "G_1") (pintype "input"))
      (node (ref "U15") (pin "19") (pinfunction "G_19") (pintype "input"))
      (node (ref "U16") (pin "1") (pinfunction "DIR_1") (pintype "input"))
      (node (ref "U17") (pin "1") (pinfunction "GND_1") (pintype "input"))
      (node (ref "U17") (pin "20") (pinfunction "GND/DAC_20") (pintype "input"))
      (node (ref "U18") (pin "1") (pinfunction "GND1_1") (pintype "input"))
      (node (ref "U18") (pin "24") (pinfunction "GND2_24") (pintype "input"))
      (node (ref "U2") (pin "1") (pinfunction "~{OE}_1") (pintype "input"))
      (node (ref "U3") (pin "1") (pinfunction "~{OE}_1") (pintype "input"))
      (node (ref "U4") (pin "1") (pinfunction "~{OE}_1") (pintype "input"))
      (node (ref "U5") (pin "1") (pinfunction "~{OE}_1") (pintype "input"))
      (node (ref "U6") (pin "1") (pinfunction "~{OE}_1") (pintype "input"))
      (node (ref "U7") (pin "5") (pinfunction "G2B_5") (pintype "input"))
      (node (ref "U8") (pin "1") (pinfunction "OC_1") (pintype "input"))
      (node (ref "Y1") (pin "4") (pinfunction "GND_4") (pintype "power_in"))
    )
    (net (code "68") (name "ID0") (class "Default")
      (node (ref "U12") (pin "2") (pinfunction "A1_2") (pintype "input"))
    )
    (net (code "69") (name "ID1") (class "Default")
      (node (ref "U12") (pin "17") (pinfunction "A4_17") (pintype "input"))
    )
    (net (code "70") (name "ID2") (class "Default")
      (node (ref "U12") (pin "4") (pinfunction "A2_4") (pintype "input"))
    )
    (net (code "71") (name "ID3") (class "Default")
      (node (ref "U12") (pin "15") (pinfunction "A3_15") (pintype "input"))
    )
    (net (code "72") (name "ID4") (class "Default")
      (node (ref "U12") (pin "6") (pinfunction "A3_6") (pintype "input"))
    )
    (net (code "73") (name "ID5") (class "Default")
      (node (ref "U12") (pin "13") (pinfunction "A2_13") (pintype "input"))
    )
    (net (code "74") (name "ID6") (class "Default")
      (node (ref "U12") (pin "8") (pinfunction "A4_8") (pintype "input"))
    )
    (net (code "75") (name "ID7") (class "Default")
      (node (ref "U12") (pin "11") (pinfunction "A1_11") (pintype "input"))
    )
    (net (code "76") (name "NTSC_SC") (class "Default")
      (node (ref "R11") (pin "1") (pinfunction "1_1") (pintype "passive"))
      (node (ref "U17") (pin "8") (pinfunction "CPUCLK/~{VDS}_8") (pintype "output"))
    )
    (net (code "77") (name "Net-(C19-1)") (class "Default")
      (node (ref "C19") (pin "P$1") (pinfunction "1_P$1") (pintype "passive"))
      (node (ref "U17") (pin "33") (pinfunction "VBB_33") (pintype "output"))
    )
    (net (code "78") (name "Net-(C20-1)") (class "Default")
      (node (ref "C20") (pin "P$1") (pinfunction "1_P$1") (pintype "passive"))
      (node (ref "U17") (pin "64") (pinfunction "XTAL2_64") (pintype "input"))
      (node (ref "Y2") (pin "1") (pinfunction "1_1") (pintype "passive"))
    )
    (net (code "79") (name "Net-(C21-1)") (class "Default")
      (node (ref "C21") (pin "P$1") (pinfunction "1_P$1") (pintype "passive"))
      (node (ref "U17") (pin "63") (pinfunction "XTAL1_63") (pintype "input"))
      (node (ref "Y2") (pin "2") (pinfunction "2_2") (pintype "passive"))
    )
    (net (code "80") (name "Net-(C23-2)") (class "Default")
      (node (ref "C23") (pin "P$2") (pinfunction "2_P$2") (pintype "passive"))
      (node (ref "U18") (pin "2") (pinfunction "RIN_2") (pintype "input"))
    )
    (net (code "81") (name "Net-(C24-2)") (class "Default")
      (node (ref "C24") (pin "P$2") (pinfunction "2_P$2") (pintype "passive"))
      (node (ref "U18") (pin "3") (pinfunction "GIN_3") (pintype "input"))
    )
    (net (code "82") (name "Net-(C25-2)") (class "Default")
      (node (ref "C25") (pin "P$2") (pinfunction "2_P$2") (pintype "passive"))
      (node (ref "U18") (pin "4") (pinfunction "BIN_4") (pintype "input"))
    )
    (net (code "83") (name "Net-(C27-1)") (class "Default")
      (node (ref "C27") (pin "P$1") (pinfunction "1_P$1") (pintype "passive"))
      (node (ref "R14") (pin "2") (pinfunction "2_2") (pintype "passive"))
      (node (ref "U18") (pin "10") (pinfunction "SYNCIN_10") (pintype "input"))
    )
    (net (code "84") (name "Net-(C30-1)") (class "Default")
      (node (ref "C30") (pin "P$1") (pinfunction "1_P$1") (pintype "passive"))
      (node (ref "R15") (pin "2") (pinfunction "2_2") (pintype "passive"))
      (node (ref "U18") (pin "17") (pinfunction "YTRAP_17") (pintype "output"))
    )
    (net (code "85") (name "Net-(C30-2)") (class "Default")
      (node (ref "C30") (pin "P$2") (pinfunction "2_P$2") (pintype "passive"))
      (node (ref "L1") (pin "1") (pinfunction "1_1") (pintype "passive"))
    )
    (net (code "86") (name "Net-(C37-Pad+)") (class "Default")
      (node (ref "C37") (pin "+") (pinfunction "+_+") (pintype "passive"))
      (node (ref "R16") (pin "2") (pinfunction "2_2") (pintype "passive"))
    )
    (net (code "87") (name "Net-(C37-Pad-)") (class "Default")
      (node (ref "C37") (pin "-") (pinfunction "-_-") (pintype "passive"))
      (node (ref "J2") (pin "3") (pinfunction "3_3") (pintype "bidirectional"))
    )
    (net (code "88") (name "Net-(C38-Pad+)") (class "Default")
      (node (ref "C38") (pin "+") (pinfunction "+_+") (pintype "passive"))
      (node (ref "R17") (pin "2") (pinfunction "2_2") (pintype "passive"))
    )
    (net (code "89") (name "Net-(C38-Pad-)") (class "Default")
      (node (ref "C38") (pin "-") (pinfunction "-_-") (pintype "passive"))
      (node (ref "J2") (pin "4") (pinfunction "4_4") (pintype "bidirectional"))
    )
    (net (code "90") (name "Net-(C39-Pad+)") (class "Default")
      (node (ref "C39") (pin "+") (pinfunction "+_+") (pintype "passive"))
      (node (ref "R18") (pin "2") (pinfunction "2_2") (pintype "passive"))
      (node (ref "R19") (pin "2") (pinfunction "2_2") (pintype "passive"))
    )
    (net (code "91") (name "Net-(C39-Pad-)") (class "Default")
      (node (ref "C39") (pin "-") (pinfunction "-_-") (pintype "passive"))
      (node (ref "J1") (pin "TIP") (pinfunction "TIP_TIP") (pintype "bidirectional"))
    )
    (net (code "92") (name "Net-(CE1-D0)") (class "Default")
      (node (ref "CE1") (pin "43") (pinfunction "D0_43") (pintype "bidirectional"))
      (node (ref "U14") (pin "2") (pinfunction "1D_2") (pintype "input"))
      (node (ref "U16") (pin "2") (pinfunction "A1_2") (pintype "bidirectional"))
    )
    (net (code "93") (name "Net-(CE1-D1)") (class "Default")
      (node (ref "CE1") (pin "44") (pinfunction "D1_44") (pintype "bidirectional"))
      (node (ref "U14") (pin "3") (pinfunction "2D_3") (pintype "input"))
      (node (ref "U16") (pin "3") (pinfunction "A2_3") (pintype "bidirectional"))
    )
    (net (code "94") (name "Net-(CE1-D2)") (class "Default")
      (node (ref "CE1") (pin "45") (pinfunction "D2_45") (pintype "bidirectional"))
      (node (ref "U14") (pin "4") (pinfunction "3D_4") (pintype "input"))
      (node (ref "U16") (pin "4") (pinfunction "A3_4") (pintype "bidirectional"))
    )
    (net (code "95") (name "Net-(CE1-D3)") (class "Default")
      (node (ref "CE1") (pin "46") (pinfunction "D3_46") (pintype "bidirectional"))
      (node (ref "U14") (pin "5") (pinfunction "4D_5") (pintype "input"))
      (node (ref "U16") (pin "5") (pinfunction "A4_5") (pintype "bidirectional"))
    )
    (net (code "96") (name "Net-(CE1-D4)") (class "Default")
      (node (ref "CE1") (pin "47") (pinfunction "D4_47") (pintype "bidirectional"))
      (node (ref "U14") (pin "6") (pinfunction "5D_6") (pintype "input"))
      (node (ref "U16") (pin "6") (pinfunction "A5_6") (pintype "bidirectional"))
    )
    (net (code "97") (name "Net-(CE1-D5)") (class "Default")
      (node (ref "CE1") (pin "48") (pinfunction "D5_48") (pintype "bidirectional"))
      (node (ref "U14") (pin "7") (pinfunction "6D_7") (pintype "input"))
      (node (ref "U16") (pin "7") (pinfunction "A6_7") (pintype "bidirectional"))
    )
    (net (code "98") (name "Net-(CE1-D6)") (class "Default")
      (node (ref "CE1") (pin "49") (pinfunction "D6_49") (pintype "bidirectional"))
      (node (ref "U14") (pin "8") (pinfunction "7D_8") (pintype "input"))
      (node (ref "U16") (pin "8") (pinfunction "A7_8") (pintype "bidirectional"))
    )
    (net (code "99") (name "Net-(CE1-D7)") (class "Default")
      (node (ref "CE1") (pin "50") (pinfunction "D7_50") (pintype "bidirectional"))
      (node (ref "U14") (pin "9") (pinfunction "8D_9") (pintype "input"))
      (node (ref "U16") (pin "9") (pinfunction "A8_9") (pintype "bidirectional"))
    )
    (net (code "100") (name "Net-(CE1-~{IRQX})") (class "Default")
      (node (ref "CE1") (pin "52") (pinfunction "~{IRQX}_52") (pintype "bidirectional"))
      (node (ref "JP3") (pin "1") (pinfunction "1_1") (pintype "passive"))
    )
    (net (code "101") (name "Net-(CE1-~{NMI})") (class "Default")
      (node (ref "CE1") (pin "61") (pinfunction "~{NMI}_61") (pintype "bidirectional"))
      (node (ref "JP3") (pin "3") (pinfunction "3_3") (pintype "passive"))
    )
    (net (code "102") (name "Net-(Q1-D)") (class "Default")
      (node (ref "JP2") (pin "1") (pinfunction "1_1") (pintype "passive"))
      (node (ref "Q1") (pin "3") (pinfunction "D_3") (pintype "passive"))
    )
    (net (code "103") (name "Net-(Q1-G)") (class "Default")
      (node (ref "Q1") (pin "2") (pinfunction "G_2") (pintype "passive"))
      (node (ref "R4") (pin "2") (pinfunction "2_2") (pintype "passive"))
    )
    (net (code "104") (name "Net-(Q2-D)") (class "Default")
      (node (ref "JP3") (pin "2") (pinfunction "2_2") (pintype "passive"))
      (node (ref "Q2") (pin "3") (pinfunction "D_3") (pintype "passive"))
    )
    (net (code "105") (name "Net-(Q2-G)") (class "Default")
      (node (ref "Q2") (pin "2") (pinfunction "G_2") (pintype "passive"))
      (node (ref "R5") (pin "2") (pinfunction "2_2") (pintype "passive"))
    )
    (net (code "106") (name "Net-(U9A-CLK)") (class "Default")
      (node (ref "JP1") (pin "2") (pinfunction "2_2") (pintype "passive"))
      (node (ref "R2") (pin "1") (pinfunction "1_1") (pintype "passive"))
      (node (ref "U9") (pin "3") (pinfunction "CLK_3") (pintype "input"))
    )
    (net (code "107") (name "Net-(U9A-CLR)") (class "Default")
      (node (ref "U9") (pin "1") (pinfunction "CLR_1") (pintype "input"))
      (node (ref "U9") (pin "8") (pinfunction "~{Q}_8") (pintype "output"))
    )
    (net (code "108") (name "Net-(U10A-O)") (class "Default")
      (node (ref "U10") (pin "12") (pinfunction "O_12") (pintype "output"))
      (node (ref "U11") (pin "9") (pinfunction "I_9") (pintype "input"))
    )
    (net (code "109") (name "Net-(U10C-O)") (class "Default")
      (node (ref "R5") (pin "1") (pinfunction "1_1") (pintype "passive"))
      (node (ref "U10") (pin "8") (pinfunction "O_8") (pintype "output"))
    )
    (net (code "110") (name "Net-(U10D-O)") (class "Default")
      (node (ref "U10") (pin "2") (pinfunction "O_2") (pintype "output"))
      (node (ref "U10") (pin "3") (pinfunction "I_3") (pintype "input"))
    )
    (net (code "111") (name "Net-(U11A-O)") (class "Default")
      (node (ref "U11") (pin "2") (pinfunction "O_2") (pintype "output"))
      (node (ref "U14") (pin "11") (pinfunction "CLK_11") (pintype "input"))
    )
    (net (code "112") (name "Net-(U11D-O)") (class "Default")
      (node (ref "U11") (pin "8") (pinfunction "O_8") (pintype "output"))
      (node (ref "U9") (pin "4") (pinfunction "PRE_4") (pintype "input"))
    )
    (net (code "113") (name "Net-(U11E-O)") (class "Default")
      (node (ref "JP1") (pin "1") (pinfunction "1_1") (pintype "passive"))
      (node (ref "U11") (pin "10") (pinfunction "O_10") (pintype "output"))
    )
    (net (code "114") (name "Net-(U13A-I0)") (class "Default")
      (node (ref "U13") (pin "1") (pinfunction "I0_1") (pintype "input"))
      (node (ref "U9") (pin "12") (pinfunction "D_12") (pintype "input"))
      (node (ref "U9") (pin "5") (pinfunction "Q_5") (pintype "output"))
    )
    (net (code "115") (name "Net-(U13A-I1)") (class "Default")
      (node (ref "U13") (pin "2") (pinfunction "I1_2") (pintype "input"))
      (node (ref "U9") (pin "9") (pinfunction "Q_9") (pintype "output"))
    )
    (net (code "116") (name "Net-(U13A-O)") (class "Default")
      (node (ref "R4") (pin "1") (pinfunction "1_1") (pintype "passive"))
      (node (ref "U13") (pin "3") (pinfunction "O_3") (pintype "output"))
    )
    (net (code "117") (name "Net-(U13C-O)") (class "Default")
      (node (ref "U13") (pin "8") (pinfunction "O_8") (pintype "output"))
      (node (ref "U14") (pin "1") (pinfunction "OC_1") (pintype "input"))
    )
    (net (code "118") (name "Net-(U13D-O)") (class "Default")
      (node (ref "U13") (pin "11") (pinfunction "O_11") (pintype "output"))
      (node (ref "U16") (pin "19") (pinfunction "G_19") (pintype "input"))
    )
    (net (code "119") (name "Net-(U17-MODE0)") (class "Default")
      (node (ref "U17") (pin "29") (pinfunction "MODE0_29") (pintype "input"))
      (node (ref "U8") (pin "2") (pinfunction "1Q_2") (pintype "tri_state"))
    )
    (net (code "120") (name "Net-(U17-MODE1)") (class "Default")
      (node (ref "U17") (pin "28") (pinfunction "MODE1_28") (pintype "input"))
      (node (ref "U8") (pin "5") (pinfunction "2Q_5") (pintype "tri_state"))
    )
    (net (code "121") (name "Net-(U18-BOUT)") (class "Default")
      (node (ref "J3") (pin "3") (pinfunction "3_3") (pintype "passive"))
      (node (ref "U18") (pin "21") (pinfunction "BOUT_21") (pintype "output"))
    )
    (net (code "122") (name "Net-(U18-COUT)") (class "Default")
      (node (ref "R17") (pin "1") (pinfunction "1_1") (pintype "passive"))
      (node (ref "U18") (pin "15") (pinfunction "COUT_15") (pintype "output"))
    )
    (net (code "123") (name "Net-(U18-CVOUT)") (class "Default")
      (node (ref "R18") (pin "1") (pinfunction "1_1") (pintype "passive"))
      (node (ref "U18") (pin "20") (pinfunction "CVOUT_20") (pintype "output"))
    )
    (net (code "124") (name "Net-(U18-GOUT)") (class "Default")
      (node (ref "J3") (pin "2") (pinfunction "2_2") (pintype "passive"))
      (node (ref "U18") (pin "22") (pinfunction "GOUT_22") (pintype "output"))
    )
    (net (code "125") (name "Net-(U18-NPIN)") (class "Default")
      (node (ref "R10") (pin "1") (pinfunction "1_1") (pintype "passive"))
      (node (ref "R13") (pin "1") (pinfunction "1_1") (pintype "passive"))
      (node (ref "U18") (pin "7") (pinfunction "NPIN_7") (pintype "input"))
    )
    (net (code "126") (name "Net-(U18-ROUT)") (class "Default")
      (node (ref "J3") (pin "1") (pinfunction "1_1") (pintype "passive"))
      (node (ref "U18") (pin "23") (pinfunction "ROUT_23") (pintype "output"))
    )
    (net (code "127") (name "Net-(U18-YOUT)") (class "Default")
      (node (ref "R16") (pin "1") (pinfunction "1_1") (pintype "passive"))
      (node (ref "U18") (pin "16") (pinfunction "YOUT_16") (pintype "output"))
    )
    (net (code "128") (name "PAL_SC") (class "Default")
      (node (ref "R12") (pin "1") (pinfunction "1_1") (pintype "passive"))
      (node (ref "U9") (pin "11") (pinfunction "CLK_11") (pintype "input"))
      (node (ref "Y1") (pin "5") (pinfunction "FO_5") (pintype "output"))
    )
    (net (code "129") (name "R") (class "Default")
      (node (ref "C23") (pin "P$1") (pinfunction "1_P$1") (pintype "passive"))
      (node (ref "J5") (pin "2") (pinfunction "2_2") (pintype "passive"))
      (node (ref "R7") (pin "2") (pinfunction "2_2") (pintype "passive"))
      (node (ref "U17") (pin "23") (pinfunction "R_23") (pintype "output"))
    )
    (net (code "130") (name "SC") (class "Default")
      (node (ref "C26") (pin "P$1") (pinfunction "1_P$1") (pintype "passive"))
      (node (ref "J5") (pin "7") (pinfunction "7_7") (pintype "passive"))
      (node (ref "R11") (pin "2") (pinfunction "2_2") (pintype "passive"))
      (node (ref "R12") (pin "2") (pinfunction "2_2") (pintype "passive"))
      (node (ref "U18") (pin "6") (pinfunction "SCIN_6") (pintype "input"))
    )
    (net (code "131") (name "VA0") (class "Default")
      (node (ref "U1") (pin "14") (pinfunction "A0_14") (pintype "input"))
      (node (ref "U17") (pin "49") (pinfunction "AD0_49") (pintype "output"))
      (node (ref "U2") (pin "14") (pinfunction "A0_14") (pintype "input"))
      (node (ref "U3") (pin "14") (pinfunction "A0_14") (pintype "input"))
      (node (ref "U4") (pin "14") (pinfunction "A0_14") (pintype "input"))
      (node (ref "U5") (pin "14") (pinfunction "A0_14") (pintype "input"))
      (node (ref "U6") (pin "14") (pinfunction "A0_14") (pintype "input"))
    )
    (net (code "132") (name "VA1") (class "Default")
      (node (ref "U1") (pin "13") (pinfunction "A1_13") (pintype "input"))
      (node (ref "U17") (pin "50") (pinfunction "AD1_50") (pintype "output"))
      (node (ref "U2") (pin "13") (pinfunction "A1_13") (pintype "input"))
      (node (ref "U3") (pin "13") (pinfunction "A1_13") (pintype "input"))
      (node (ref "U4") (pin "13") (pinfunction "A1_13") (pintype "input"))
      (node (ref "U5") (pin "13") (pinfunction "A1_13") (pintype "input"))
      (node (ref "U6") (pin "13") (pinfunction "A1_13") (pintype "input"))
    )
    (net (code "133") (name "VA2") (class "Default")
      (node (ref "U1") (pin "6") (pinfunction "A6_6") (pintype "input"))
      (node (ref "U17") (pin "51") (pinfunction "AD2_51") (pintype "output"))
      (node (ref "U2") (pin "6") (pinfunction "A6_6") (pintype "input"))
      (node (ref "U3") (pin "6") (pinfunction "A6_6") (pintype "input"))
      (node (ref "U4") (pin "6") (pinfunction "A6_6") (pintype "input"))
      (node (ref "U5") (pin "6") (pinfunction "A6_6") (pintype "input"))
      (node (ref "U6") (pin "6") (pinfunction "A6_6") (pintype "input"))
    )
    (net (code "134") (name "VA3") (class "Default")
      (node (ref "U1") (pin "12") (pinfunction "A2_12") (pintype "input"))
      (node (ref "U17") (pin "52") (pinfunction "AD3_52") (pintype "output"))
      (node (ref "U2") (pin "12") (pinfunction "A2_12") (pintype "input"))
      (node (ref "U3") (pin "12") (pinfunction "A2_12") (pintype "input"))
      (node (ref "U4") (pin "12") (pinfunction "A2_12") (pintype "input"))
      (node (ref "U5") (pin "12") (pinfunction "A2_12") (pintype "input"))
      (node (ref "U6") (pin "12") (pinfunction "A2_12") (pintype "input"))
    )
    (net (code "135") (name "VA4") (class "Default")
      (node (ref "U1") (pin "7") (pinfunction "A5_7") (pintype "input"))
      (node (ref "U17") (pin "53") (pinfunction "AD4_53") (pintype "output"))
      (node (ref "U2") (pin "7") (pinfunction "A5_7") (pintype "input"))
      (node (ref "U3") (pin "7") (pinfunction "A5_7") (pintype "input"))
      (node (ref "U4") (pin "7") (pinfunction "A5_7") (pintype "input"))
      (node (ref "U5") (pin "7") (pinfunction "A5_7") (pintype "input"))
      (node (ref "U6") (pin "7") (pinfunction "A5_7") (pintype "input"))
    )
    (net (code "136") (name "VA5") (class "Default")
      (node (ref "U1") (pin "11") (pinfunction "A3_11") (pintype "input"))
      (node (ref "U17") (pin "54") (pinfunction "AD5_54") (pintype "output"))
      (node (ref "U2") (pin "11") (pinfunction "A3_11") (pintype "input"))
      (node (ref "U3") (pin "11") (pinfunction "A3_11") (pintype "input"))
      (node (ref "U4") (pin "11") (pinfunction "A3_11") (pintype "input"))
      (node (ref "U5") (pin "11") (pinfunction "A3_11") (pintype "input"))
      (node (ref "U6") (pin "11") (pinfunction "A3_11") (pintype "input"))
    )
    (net (code "137") (name "VA6") (class "Default")
      (node (ref "U1") (pin "8") (pinfunction "A4_8") (pintype "input"))
      (node (ref "U17") (pin "55") (pinfunction "AD6_55") (pintype "output"))
      (node (ref "U2") (pin "8") (pinfunction "A4_8") (pintype "input"))
      (node (ref "U3") (pin "8") (pinfunction "A4_8") (pintype "input"))
      (node (ref "U4") (pin "8") (pinfunction "A4_8") (pintype "input"))
      (node (ref "U5") (pin "8") (pinfunction "A4_8") (pintype "input"))
      (node (ref "U6") (pin "8") (pinfunction "A4_8") (pintype "input"))
    )
    (net (code "138") (name "VA7") (class "Default")
      (node (ref "U1") (pin "10") (pinfunction "A7_10") (pintype "input"))
      (node (ref "U17") (pin "56") (pinfunction "AD7_56") (pintype "output"))
      (node (ref "U2") (pin "10") (pinfunction "A7_10") (pintype "input"))
      (node (ref "U3") (pin "10") (pinfunction "A7_10") (pintype "input"))
      (node (ref "U4") (pin "10") (pinfunction "A7_10") (pintype "input"))
      (node (ref "U5") (pin "10") (pinfunction "A7_10") (pintype "input"))
      (node (ref "U6") (pin "10") (pinfunction "A7_10") (pintype "input"))
    )
    (net (code "139") (name "VCC") (class "Default")
      (node (ref "C1") (pin "P$1") (pinfunction "1_P$1") (pintype "passive"))
      (node (ref "C10") (pin "P$1") (pinfunction "1_P$1") (pintype "passive"))
      (node (ref "C11") (pin "P$1") (pinfunction "1_P$1") (pintype "passive"))
      (node (ref "C12") (pin "P$1") (pinfunction "1_P$1") (pintype "passive"))
      (node (ref "C13") (pin "P$1") (pinfunction "1_P$1") (pintype "passive"))
      (node (ref "C14") (pin "P$1") (pinfunction "1_P$1") (pintype "passive"))
      (node (ref "C15") (pin "P$1") (pinfunction "1_P$1") (pintype "passive"))
      (node (ref "C16") (pin "P$1") (pinfunction "1_P$1") (pintype "passive"))
      (node (ref "C17") (pin "P$1") (pinfunction "1_P$1") (pintype "passive"))
      (node (ref "C18") (pin "P$1") (pinfunction "1_P$1") (pintype "passive"))
      (node (ref "C2") (pin "P$1") (pinfunction "1_P$1") (pintype "passive"))
      (node (ref "C22") (pin "P$1") (pinfunction "1_P$1") (pintype "passive"))
      (node (ref "C28") (pin "P$1") (pinfunction "1_P$1") (pintype "passive"))
      (node (ref "C29") (pin "1") (pinfunction "1_1") (pintype "passive"))
      (node (ref "C3") (pin "P$1") (pinfunction "1_P$1") (pintype "passive"))
      (node (ref "C31") (pin "+") (pinfunction "+_+") (pintype "passive"))
      (node (ref "C32") (pin "+") (pinfunction "+_+") (pintype "passive"))
      (node (ref "C33") (pin "+") (pinfunction "+_+") (pintype "passive"))
      (node (ref "C34") (pin "+") (pinfunction "+_+") (pintype "passive"))
      (node (ref "C35") (pin "+") (pinfunction "+_+") (pintype "passive"))
      (node (ref "C36") (pin "+") (pinfunction "+_+") (pintype "passive"))
      (node (ref "C4") (pin "P$1") (pinfunction "1_P$1") (pintype "passive"))
      (node (ref "C5") (pin "P$1") (pinfunction "1_P$1") (pintype "passive"))
      (node (ref "C6") (pin "P$1") (pinfunction "1_P$1") (pintype "passive"))
      (node (ref "C7") (pin "P$1") (pinfunction "1_P$1") (pintype "passive"))
      (node (ref "C8") (pin "P$1") (pinfunction "1_P$1") (pintype "passive"))
      (node (ref "C9") (pin "P$1") (pinfunction "1_P$1") (pintype "passive"))
      (node (ref "CE1") (pin "5") (pinfunction "+5V_5") (pintype "bidirectional"))
      (node (ref "CE1") (pin "6") (pinfunction "+5V_6") (pintype "bidirectional"))
      (node (ref "J5") (pin "4") (pinfunction "4_4") (pintype "passive"))
      (node (ref "R1") (pin "2") (pinfunction "2_2") (pintype "passive"))
      (node (ref "R10") (pin "2") (pinfunction "2_2") (pintype "passive"))
      (node (ref "R15") (pin "1") (pinfunction "1_1") (pintype "passive"))
      (node (ref "R2") (pin "2") (pinfunction "2_2") (pintype "passive"))
      (node (ref "R3") (pin "2") (pinfunction "2_2") (pintype "passive"))
      (node (ref "R6") (pin "2") (pinfunction "2_2") (pintype "passive"))
      (node (ref "RN1") (pin "1") (pinfunction "1_1") (pintype "passive"))
      (node (ref "U10") (pin "11") (pinfunction "I_11") (pintype "input"))
      (node (ref "U10") (pin "5") (pinfunction "I_5") (pintype "input"))
      (node (ref "U11") (pin "13") (pinfunction "I_13") (pintype "input"))
      (node (ref "U11") (pin "3") (pinfunction "I_3") (pintype "input"))
      (node (ref "U11") (pin "5") (pinfunction "I_5") (pintype "input"))
      (node (ref "U13") (pin "4") (pinfunction "I0_4") (pintype "input"))
      (node (ref "U13") (pin "5") (pinfunction "I1_5") (pintype "input"))
      (node (ref "U15") (pin "17") (pinfunction "A4_17") (pintype "input"))
      (node (ref "U15") (pin "4") (pinfunction "A2_4") (pintype "input"))
      (node (ref "U17") (pin "21") (pinfunction "VDD/DAC_21") (pintype "input"))
      (node (ref "U17") (pin "27") (pinfunction "~{HRESET}_27") (pintype "input"))
      (node (ref "U17") (pin "4") (pinfunction "~{VRESET}_4") (pintype "input"))
      (node (ref "U17") (pin "58") (pinfunction "VDD_58") (pintype "input"))
      (node (ref "U18") (pin "12") (pinfunction "VCC1_12") (pintype "input"))
      (node (ref "U18") (pin "19") (pinfunction "VCC2_19") (pintype "input"))
      (node (ref "U7") (pin "6") (pinfunction "G1_6") (pintype "input"))
      (node (ref "U8") (pin "13") (pinfunction "5D_13") (pintype "input"))
      (node (ref "U8") (pin "14") (pinfunction "6D_14") (pintype "input"))
      (node (ref "U8") (pin "17") (pinfunction "7D_17") (pintype "input"))
      (node (ref "U8") (pin "18") (pinfunction "8D_18") (pintype "input"))
      (node (ref "U8") (pin "8") (pinfunction "4D_8") (pintype "input"))
      (node (ref "U9") (pin "10") (pinfunction "PRE_10") (pintype "input"))
      (node (ref "U9") (pin "2") (pinfunction "D_2") (pintype "input"))
      (node (ref "Y1") (pin "1") (pinfunction "OE_1") (pintype "input"))
      (node (ref "Y1") (pin "8") (pinfunction "VCC_8") (pintype "power_in"))
    )
    (net (code "140") (name "VD0") (class "Default")
      (node (ref "U17") (pin "41") (pinfunction "RD0_41") (pintype "bidirectional"))
      (node (ref "U4") (pin "17") (pinfunction "D3_17") (pintype "bidirectional"))
      (node (ref "U5") (pin "17") (pinfunction "D3_17") (pintype "bidirectional"))
      (node (ref "U6") (pin "17") (pinfunction "D3_17") (pintype "bidirectional"))
    )
    (net (code "141") (name "VD1") (class "Default")
      (node (ref "U17") (pin "42") (pinfunction "RD1_42") (pintype "bidirectional"))
      (node (ref "U4") (pin "2") (pinfunction "D0_2") (pintype "bidirectional"))
      (node (ref "U5") (pin "2") (pinfunction "D0_2") (pintype "bidirectional"))
      (node (ref "U6") (pin "2") (pinfunction "D0_2") (pintype "bidirectional"))
    )
    (net (code "142") (name "VD2") (class "Default")
      (node (ref "U17") (pin "43") (pinfunction "RD2_43") (pintype "bidirectional"))
      (node (ref "U4") (pin "3") (pinfunction "D1_3") (pintype "bidirectional"))
      (node (ref "U5") (pin "3") (pinfunction "D1_3") (pintype "bidirectional"))
      (node (ref "U6") (pin "3") (pinfunction "D1_3") (pintype "bidirectional"))
    )
    (net (code "143") (name "VD3") (class "Default")
      (node (ref "U17") (pin "44") (pinfunction "RD3_44") (pintype "bidirectional"))
      (node (ref "U4") (pin "15") (pinfunction "D2_15") (pintype "bidirectional"))
      (node (ref "U5") (pin "15") (pinfunction "D2_15") (pintype "bidirectional"))
      (node (ref "U6") (pin "15") (pinfunction "D2_15") (pintype "bidirectional"))
    )
    (net (code "144") (name "VD4") (class "Default")
      (node (ref "U1") (pin "2") (pinfunction "D0_2") (pintype "bidirectional"))
      (node (ref "U17") (pin "45") (pinfunction "RD4_45") (pintype "bidirectional"))
      (node (ref "U2") (pin "2") (pinfunction "D0_2") (pintype "bidirectional"))
      (node (ref "U3") (pin "2") (pinfunction "D0_2") (pintype "bidirectional"))
    )
    (net (code "145") (name "VD5") (class "Default")
      (node (ref "U1") (pin "3") (pinfunction "D1_3") (pintype "bidirectional"))
      (node (ref "U17") (pin "46") (pinfunction "RD5_46") (pintype "bidirectional"))
      (node (ref "U2") (pin "3") (pinfunction "D1_3") (pintype "bidirectional"))
      (node (ref "U3") (pin "3") (pinfunction "D1_3") (pintype "bidirectional"))
    )
    (net (code "146") (name "VD6") (class "Default")
      (node (ref "U1") (pin "15") (pinfunction "D2_15") (pintype "bidirectional"))
      (node (ref "U17") (pin "47") (pinfunction "RD6_47") (pintype "bidirectional"))
      (node (ref "U2") (pin "15") (pinfunction "D2_15") (pintype "bidirectional"))
      (node (ref "U3") (pin "15") (pinfunction "D2_15") (pintype "bidirectional"))
    )
    (net (code "147") (name "VD7") (class "Default")
      (node (ref "U1") (pin "17") (pinfunction "D3_17") (pintype "bidirectional"))
      (node (ref "U17") (pin "48") (pinfunction "RD7_48") (pintype "bidirectional"))
      (node (ref "U2") (pin "17") (pinfunction "D3_17") (pintype "bidirectional"))
      (node (ref "U3") (pin "17") (pinfunction "D3_17") (pintype "bidirectional"))
    )
    (net (code "148") (name "VR{slash}~{W}") (class "Default")
      (node (ref "U1") (pin "4") (pinfunction "~{WE}_4") (pintype "input"))
      (node (ref "U17") (pin "57") (pinfunction "R/~{W}_57") (pintype "output"))
      (node (ref "U2") (pin "4") (pinfunction "~{WE}_4") (pintype "input"))
      (node (ref "U3") (pin "4") (pinfunction "~{WE}_4") (pintype "input"))
      (node (ref "U4") (pin "4") (pinfunction "~{WE}_4") (pintype "input"))
      (node (ref "U5") (pin "4") (pinfunction "~{WE}_4") (pintype "input"))
      (node (ref "U6") (pin "4") (pinfunction "~{WE}_4") (pintype "input"))
    )
    (net (code "149") (name "unconnected-(CE1-+3.3V-Pad2)") (class "Default")
      (node (ref "CE1") (pin "2") (pinfunction "+3.3V_2") (pintype "bidirectional"))
    )
    (net (code "150") (name "unconnected-(CE1-+5VSB-Pad8)") (class "Default")
      (node (ref "CE1") (pin "8") (pinfunction "+5VSB_8") (pintype "bidirectional"))
    )
    (net (code "151") (name "unconnected-(CE1-+12V-Pad1)") (class "Default")
      (node (ref "CE1") (pin "1") (pinfunction "+12V_1") (pintype "bidirectional"))
    )
    (net (code "152") (name "unconnected-(CE1--12V-Pad7)") (class "Default")
      (node (ref "CE1") (pin "7") (pinfunction "-12V_7") (pintype "bidirectional"))
    )
    (net (code "153") (name "unconnected-(CE1-A2-Pad25)") (class "Default")
      (node (ref "CE1") (pin "25") (pinfunction "A2_25") (pintype "bidirectional"))
    )
    (net (code "154") (name "unconnected-(CE1-A3-Pad26)") (class "Default")
      (node (ref "CE1") (pin "26") (pinfunction "A3_26") (pintype "bidirectional"))
    )
    (net (code "155") (name "unconnected-(CE1-A4-Pad27)") (class "Default")
      (node (ref "CE1") (pin "27") (pinfunction "A4_27") (pintype "bidirectional"))
    )
    (net (code "156") (name "unconnected-(CE1-A5-Pad28)") (class "Default")
      (node (ref "CE1") (pin "28") (pinfunction "A5_28") (pintype "bidirectional"))
    )
    (net (code "157") (name "unconnected-(CE1-A6-Pad29)") (class "Default")
      (node (ref "CE1") (pin "29") (pinfunction "A6_29") (pintype "bidirectional"))
    )
    (net (code "158") (name "unconnected-(CE1-A8-Pad31)") (class "Default")
      (node (ref "CE1") (pin "31") (pinfunction "A8_31") (pintype "bidirectional"))
    )
    (net (code "159") (name "unconnected-(CE1-A9-Pad32)") (class "Default")
      (node (ref "CE1") (pin "32") (pinfunction "A9_32") (pintype "bidirectional"))
    )
    (net (code "160") (name "unconnected-(CE1-A10-Pad33)") (class "Default")
      (node (ref "CE1") (pin "33") (pinfunction "A10_33") (pintype "bidirectional"))
    )
    (net (code "161") (name "unconnected-(CE1-A11-Pad34)") (class "Default")
      (node (ref "CE1") (pin "34") (pinfunction "A11_34") (pintype "bidirectional"))
    )
    (net (code "162") (name "unconnected-(CE1-A12-Pad35)") (class "Default")
      (node (ref "CE1") (pin "35") (pinfunction "A12_35") (pintype "bidirectional"))
    )
    (net (code "163") (name "unconnected-(CE1-A13-Pad36)") (class "Default")
      (node (ref "CE1") (pin "36") (pinfunction "A13_36") (pintype "bidirectional"))
    )
    (net (code "164") (name "unconnected-(CE1-A14-Pad37)") (class "Default")
      (node (ref "CE1") (pin "37") (pinfunction "A14_37") (pintype "bidirectional"))
    )
    (net (code "165") (name "unconnected-(CE1-A15-Pad38)") (class "Default")
      (node (ref "CE1") (pin "38") (pinfunction "A15_38") (pintype "bidirectional"))
    )
    (net (code "166") (name "unconnected-(CE1-A16-Pad39)") (class "Default")
      (node (ref "CE1") (pin "39") (pinfunction "A16_39") (pintype "bidirectional"))
    )
    (net (code "167") (name "unconnected-(CE1-A17-Pad40)") (class "Default")
      (node (ref "CE1") (pin "40") (pinfunction "A17_40") (pintype "bidirectional"))
    )
    (net (code "168") (name "unconnected-(CE1-A18-Pad41)") (class "Default")
      (node (ref "CE1") (pin "41") (pinfunction "A18_41") (pintype "bidirectional"))
    )
    (net (code "169") (name "unconnected-(CE1-A19-Pad42)") (class "Default")
      (node (ref "CE1") (pin "42") (pinfunction "A19_42") (pintype "bidirectional"))
    )
    (net (code "170") (name "unconnected-(CE1-CLK-Pad15)") (class "Default")
      (node (ref "CE1") (pin "15") (pinfunction "CLK_15") (pintype "bidirectional"))
    )
    (net (code "171") (name "unconnected-(CE1-~{BUSACK}-Pad20)") (class "Default")
      (node (ref "CE1") (pin "20") (pinfunction "~{BUSACK}_20") (pintype "bidirectional"))
    )
    (net (code "172") (name "unconnected-(CE1-~{BUSRQ}-Pad10)") (class "Default")
      (node (ref "CE1") (pin "10") (pinfunction "~{BUSRQ}_10") (pintype "bidirectional"))
    )
    (net (code "173") (name "unconnected-(CE1-~{CBR}-Pad12)") (class "Default")
      (node (ref "CE1") (pin "12") (pinfunction "~{CBR}_12") (pintype "bidirectional"))
    )
    (net (code "174") (name "unconnected-(CE1-~{CINH}-Pad13)") (class "Default")
      (node (ref "CE1") (pin "13") (pinfunction "~{CINH}_13") (pintype "bidirectional"))
    )
    (net (code "175") (name "unconnected-(CE1-~{FETCH}-Pad19)") (class "Default")
      (node (ref "CE1") (pin "19") (pinfunction "~{FETCH}_19") (pintype "bidirectional"))
    )
    (net (code "176") (name "unconnected-(CE1-~{HALT}-Pad17)") (class "Default")
      (node (ref "CE1") (pin "17") (pinfunction "~{HALT}_17") (pintype "bidirectional"))
    )
    (net (code "177") (name "unconnected-(CE1-~{INH}-Pad11)") (class "Default")
      (node (ref "CE1") (pin "11") (pinfunction "~{INH}_11") (pintype "bidirectional"))
    )
    (net (code "178") (name "unconnected-(CE1-~{INT}-Pad51)") (class "Default")
      (node (ref "CE1") (pin "51") (pinfunction "~{INT}_51") (pintype "bidirectional"))
    )
    (net (code "179") (name "unconnected-(CE1-~{IOSEL}-Pad16)") (class "Default")
      (node (ref "CE1") (pin "16") (pinfunction "~{IOSEL}_16") (pintype "bidirectional"))
    )
    (net (code "180") (name "unconnected-(CE1-~{IRQ0}-Pad53)") (class "Default")
      (node (ref "CE1") (pin "53") (pinfunction "~{IRQ0}_53") (pintype "bidirectional"))
    )
    (net (code "181") (name "unconnected-(CE1-~{IRQ1}-Pad54)") (class "Default")
      (node (ref "CE1") (pin "54") (pinfunction "~{IRQ1}_54") (pintype "bidirectional"))
    )
    (net (code "182") (name "unconnected-(CE1-~{IRQ2}-Pad55)") (class "Default")
      (node (ref "CE1") (pin "55") (pinfunction "~{IRQ2}_55") (pintype "bidirectional"))
    )
    (net (code "183") (name "unconnected-(CE1-~{IRQ3}-Pad56)") (class "Default")
      (node (ref "CE1") (pin "56") (pinfunction "~{IRQ3}_56") (pintype "bidirectional"))
    )
    (net (code "184") (name "unconnected-(CE1-~{IRQ4}-Pad57)") (class "Default")
      (node (ref "CE1") (pin "57") (pinfunction "~{IRQ4}_57") (pintype "bidirectional"))
    )
    (net (code "185") (name "unconnected-(CE1-~{IRQ5}-Pad58)") (class "Default")
      (node (ref "CE1") (pin "58") (pinfunction "~{IRQ5}_58") (pintype "bidirectional"))
    )
    (net (code "186") (name "unconnected-(CE1-~{IRQ6}-Pad59)") (class "Default")
      (node (ref "CE1") (pin "59") (pinfunction "~{IRQ6}_59") (pintype "bidirectional"))
    )
    (net (code "187") (name "unconnected-(CE1-~{IRQ7}-Pad60)") (class "Default")
      (node (ref "CE1") (pin "60") (pinfunction "~{IRQ7}_60") (pintype "bidirectional"))
    )
    (net (code "188") (name "unconnected-(J1-PadSHUNT)") (class "Default")
      (node (ref "J1") (pin "SHUNT") (pinfunction "SHUNT_SHUNT") (pintype "bidirectional"))
    )
    (net (code "189") (name "unconnected-(U7A-Y0-Pad15)") (class "Default")
      (node (ref "U7") (pin "15") (pinfunction "Y0_15") (pintype "output"))
    )
    (net (code "190") (name "unconnected-(U7A-Y3-Pad12)") (class "Default")
      (node (ref "U7") (pin "12") (pinfunction "Y3_12") (pintype "output"))
    )
    (net (code "191") (name "unconnected-(U7A-Y4-Pad11)") (class "Default")
      (node (ref "U7") (pin "11") (pinfunction "Y4_11") (pintype "output"))
    )
    (net (code "192") (name "unconnected-(U7A-Y5-Pad10)") (class "Default")
      (node (ref "U7") (pin "10") (pinfunction "Y5_10") (pintype "output"))
    )
    (net (code "193") (name "unconnected-(U7A-Y7-Pad7)") (class "Default")
      (node (ref "U7") (pin "7") (pinfunction "Y7_7") (pintype "output"))
    )
    (net (code "194") (name "unconnected-(U8A-3Q-Pad6)") (class "Default")
      (node (ref "U8") (pin "6") (pinfunction "3Q_6") (pintype "tri_state"))
    )
    (net (code "195") (name "unconnected-(U8A-4Q-Pad9)") (class "Default")
      (node (ref "U8") (pin "9") (pinfunction "4Q_9") (pintype "tri_state"))
    )
    (net (code "196") (name "unconnected-(U8A-5Q-Pad12)") (class "Default")
      (node (ref "U8") (pin "12") (pinfunction "5Q_12") (pintype "tri_state"))
    )
    (net (code "197") (name "unconnected-(U8A-6Q-Pad15)") (class "Default")
      (node (ref "U8") (pin "15") (pinfunction "6Q_15") (pintype "tri_state"))
    )
    (net (code "198") (name "unconnected-(U8A-7Q-Pad16)") (class "Default")
      (node (ref "U8") (pin "16") (pinfunction "7Q_16") (pintype "tri_state"))
    )
    (net (code "199") (name "unconnected-(U8A-8Q-Pad19)") (class "Default")
      (node (ref "U8") (pin "19") (pinfunction "8Q_19") (pintype "tri_state"))
    )
    (net (code "200") (name "unconnected-(U9A-~{Q}-Pad6)") (class "Default")
      (node (ref "U9") (pin "6") (pinfunction "~{Q}_6") (pintype "output"))
    )
    (net (code "201") (name "unconnected-(U10B-O-Pad10)") (class "Default")
      (node (ref "U10") (pin "10") (pinfunction "O_10") (pintype "output"))
    )
    (net (code "202") (name "unconnected-(U10F-O-Pad6)") (class "Default")
      (node (ref "U10") (pin "6") (pinfunction "O_6") (pintype "output"))
    )
    (net (code "203") (name "unconnected-(U11B-O-Pad4)") (class "Default")
      (node (ref "U11") (pin "4") (pinfunction "O_4") (pintype "output"))
    )
    (net (code "204") (name "unconnected-(U11C-O-Pad6)") (class "Default")
      (node (ref "U11") (pin "6") (pinfunction "O_6") (pintype "output"))
    )
    (net (code "205") (name "unconnected-(U11F-O-Pad12)") (class "Default")
      (node (ref "U11") (pin "12") (pinfunction "O_12") (pintype "output"))
    )
    (net (code "206") (name "unconnected-(U13B-O-Pad6)") (class "Default")
      (node (ref "U13") (pin "6") (pinfunction "O_6") (pintype "output"))
    )
    (net (code "207") (name "unconnected-(U15A-Y2-Pad16)") (class "Default")
      (node (ref "U15") (pin "16") (pinfunction "Y2_16") (pintype "tri_state"))
    )
    (net (code "208") (name "unconnected-(U15B-Y4-Pad3)") (class "Default")
      (node (ref "U15") (pin "3") (pinfunction "Y4_3") (pintype "tri_state"))
    )
    (net (code "209") (name "unconnected-(U17-BLEO-Pad7)") (class "Default")
      (node (ref "U17") (pin "7") (pinfunction "BLEO_7") (pintype "output"))
    )
    (net (code "210") (name "unconnected-(U17-~{HSYNC}-Pad5)") (class "Default")
      (node (ref "U17") (pin "5") (pinfunction "~{HSYNC}_5") (pintype "output"))
    )
    (net (code "211") (name "unconnected-(U17-~{YS}-Pad10)") (class "Default")
      (node (ref "U17") (pin "10") (pinfunction "~{YS}_10") (pintype "output"))
    )
    (net (code "212") (name "unconnected-(U18-BFOUT-Pad8)") (class "Default")
      (node (ref "U18") (pin "8") (pinfunction "BFOUT_8") (pintype "output"))
    )
    (net (code "213") (name "~{BCSX}") (class "Default")
      (node (ref "CE1") (pin "9") (pinfunction "~{CSX}_9") (pintype "bidirectional"))
      (node (ref "U15") (pin "2") (pinfunction "A1_2") (pintype "input"))
    )
    (net (code "214") (name "~{BRD}") (class "Default")
      (node (ref "CE1") (pin "21") (pinfunction "~{RD}_21") (pintype "bidirectional"))
      (node (ref "U15") (pin "15") (pinfunction "A3_15") (pintype "input"))
    )
    (net (code "215") (name "~{BRST}") (class "Default")
      (node (ref "CE1") (pin "14") (pinfunction "~{RST}_14") (pintype "bidirectional"))
      (node (ref "U10") (pin "1") (pinfunction "I_1") (pintype "input"))
    )
    (net (code "216") (name "~{BWAIT}") (class "Default")
      (node (ref "CE1") (pin "18") (pinfunction "~{WAIT}_18") (pintype "bidirectional"))
      (node (ref "JP2") (pin "2") (pinfunction "2_2") (pintype "passive"))
    )
    (net (code "217") (name "~{BWR}") (class "Default")
      (node (ref "CE1") (pin "22") (pinfunction "~{WR}_22") (pintype "bidirectional"))
      (node (ref "U15") (pin "6") (pinfunction "A3_6") (pintype "input"))
    )
    (net (code "218") (name "~{CSIDR}") (class "Default")
      (node (ref "U12") (pin "1") (pinfunction "G_1") (pintype "input"))
      (node (ref "U12") (pin "19") (pinfunction "G_19") (pintype "input"))
      (node (ref "U7") (pin "9") (pinfunction "Y6_9") (pintype "output"))
    )
    (net (code "219") (name "~{CSVR}") (class "Default")
      (node (ref "U17") (pin "31") (pinfunction "~{CSR}_31") (pintype "input"))
      (node (ref "U7") (pin "13") (pinfunction "Y2_13") (pintype "output"))
    )
    (net (code "220") (name "~{CSVW}") (class "Default")
      (node (ref "U17") (pin "30") (pinfunction "~{CSW}_30") (pintype "input"))
      (node (ref "U7") (pin "14") (pinfunction "Y1_14") (pintype "output"))
    )
    (net (code "221") (name "~{CSX}") (class "Default")
      (node (ref "U11") (pin "11") (pinfunction "I_11") (pintype "input"))
      (node (ref "U13") (pin "13") (pinfunction "I1_13") (pintype "input"))
      (node (ref "U13") (pin "9") (pinfunction "I0_9") (pintype "input"))
      (node (ref "U15") (pin "18") (pinfunction "Y1_18") (pintype "tri_state"))
      (node (ref "U7") (pin "4") (pinfunction "G2A_4") (pintype "input"))
      (node (ref "U8") (pin "11") (pinfunction "ENC_11") (pintype "input"))
    )
    (net (code "222") (name "~{CSYNC}") (class "Default")
      (node (ref "J5") (pin "8") (pinfunction "8_8") (pintype "passive"))
      (node (ref "R14") (pin "1") (pinfunction "1_1") (pintype "passive"))
      (node (ref "U17") (pin "6") (pinfunction "~{CSYNC}_6") (pintype "output"))
    )
    (net (code "223") (name "~{DHCLK}") (class "Default")
      (node (ref "J4") (pin "11") (pinfunction "11_11") (pintype "passive"))
      (node (ref "U17") (pin "2") (pinfunction "~{DHCLK}_2") (pintype "output"))
    )
    (net (code "224") (name "~{DLCLK}") (class "Default")
      (node (ref "J4") (pin "10") (pinfunction "10_10") (pintype "passive"))
      (node (ref "R6") (pin "1") (pinfunction "1_1") (pintype "passive"))
      (node (ref "U17") (pin "3") (pinfunction "~{DLCLK}_3") (pintype "bidirectional"))
    )
    (net (code "225") (name "~{RD}") (class "Default")
      (node (ref "U13") (pin "12") (pinfunction "I0_12") (pintype "input"))
      (node (ref "U15") (pin "5") (pinfunction "Y3_5") (pintype "tri_state"))
      (node (ref "U7") (pin "1") (pinfunction "A_1") (pintype "input"))
    )
    (net (code "226") (name "~{RST}") (class "Default")
      (node (ref "U10") (pin "4") (pinfunction "O_4") (pintype "output"))
      (node (ref "U17") (pin "9") (pinfunction "~{RESET}_9") (pintype "input"))
      (node (ref "U9") (pin "13") (pinfunction "CLR_13") (pintype "input"))
    )
    (net (code "227") (name "~{VCAS0}") (class "Default")
      (node (ref "U1") (pin "16") (pinfunction "~{CAS}_16") (pintype "input"))
      (node (ref "U17") (pin "61") (pinfunction "~{CAS0}_61") (pintype "output"))
      (node (ref "U4") (pin "16") (pinfunction "~{CAS}_16") (pintype "input"))
    )
    (net (code "228") (name "~{VCAS1}") (class "Default")
      (node (ref "U17") (pin "60") (pinfunction "~{CAS1}_60") (pintype "output"))
      (node (ref "U2") (pin "16") (pinfunction "~{CAS}_16") (pintype "input"))
      (node (ref "U5") (pin "16") (pinfunction "~{CAS}_16") (pintype "input"))
    )
    (net (code "229") (name "~{VCAS2}") (class "Default")
      (node (ref "U17") (pin "59") (pinfunction "~{CASX}_59") (pintype "output"))
      (node (ref "U3") (pin "16") (pinfunction "~{CAS}_16") (pintype "input"))
      (node (ref "U6") (pin "16") (pinfunction "~{CAS}_16") (pintype "input"))
    )
    (net (code "230") (name "~{VINT}") (class "Default")
      (node (ref "R1") (pin "1") (pinfunction "1_1") (pintype "passive"))
      (node (ref "U10") (pin "9") (pinfunction "I_9") (pintype "input"))
      (node (ref "U17") (pin "25") (pinfunction "~{INT}_25") (pintype "output"))
    )
    (net (code "231") (name "~{VRAS}") (class "Default")
      (node (ref "U1") (pin "5") (pinfunction "~{RAS}_5") (pintype "input"))
      (node (ref "U17") (pin "62") (pinfunction "~{RAS}_62") (pintype "output"))
      (node (ref "U2") (pin "5") (pinfunction "~{RAS}_5") (pintype "input"))
      (node (ref "U3") (pin "5") (pinfunction "~{RAS}_5") (pintype "input"))
      (node (ref "U4") (pin "5") (pinfunction "~{RAS}_5") (pintype "input"))
      (node (ref "U5") (pin "5") (pinfunction "~{RAS}_5") (pintype "input"))
      (node (ref "U6") (pin "5") (pinfunction "~{RAS}_5") (pintype "input"))
    )
    (net (code "232") (name "~{VWAIT}") (class "Default")
      (node (ref "R3") (pin "1") (pinfunction "1_1") (pintype "passive"))
      (node (ref "U10") (pin "13") (pinfunction "I_13") (pintype "input"))
      (node (ref "U17") (pin "26") (pinfunction "~{WAIT}_26") (pintype "output"))
    )
    (net (code "233") (name "~{WR}") (class "Default")
      (node (ref "U11") (pin "1") (pinfunction "I_1") (pintype "input"))
      (node (ref "U13") (pin "10") (pinfunction "I1_10") (pintype "input"))
      (node (ref "U15") (pin "14") (pinfunction "Y3_14") (pintype "tri_state"))
      (node (ref "U7") (pin "2") (pinfunction "B_2") (pintype "input"))
    )
  )
)
